# Send3.net
KiCad netlist of a schematic drawn in EAGLE
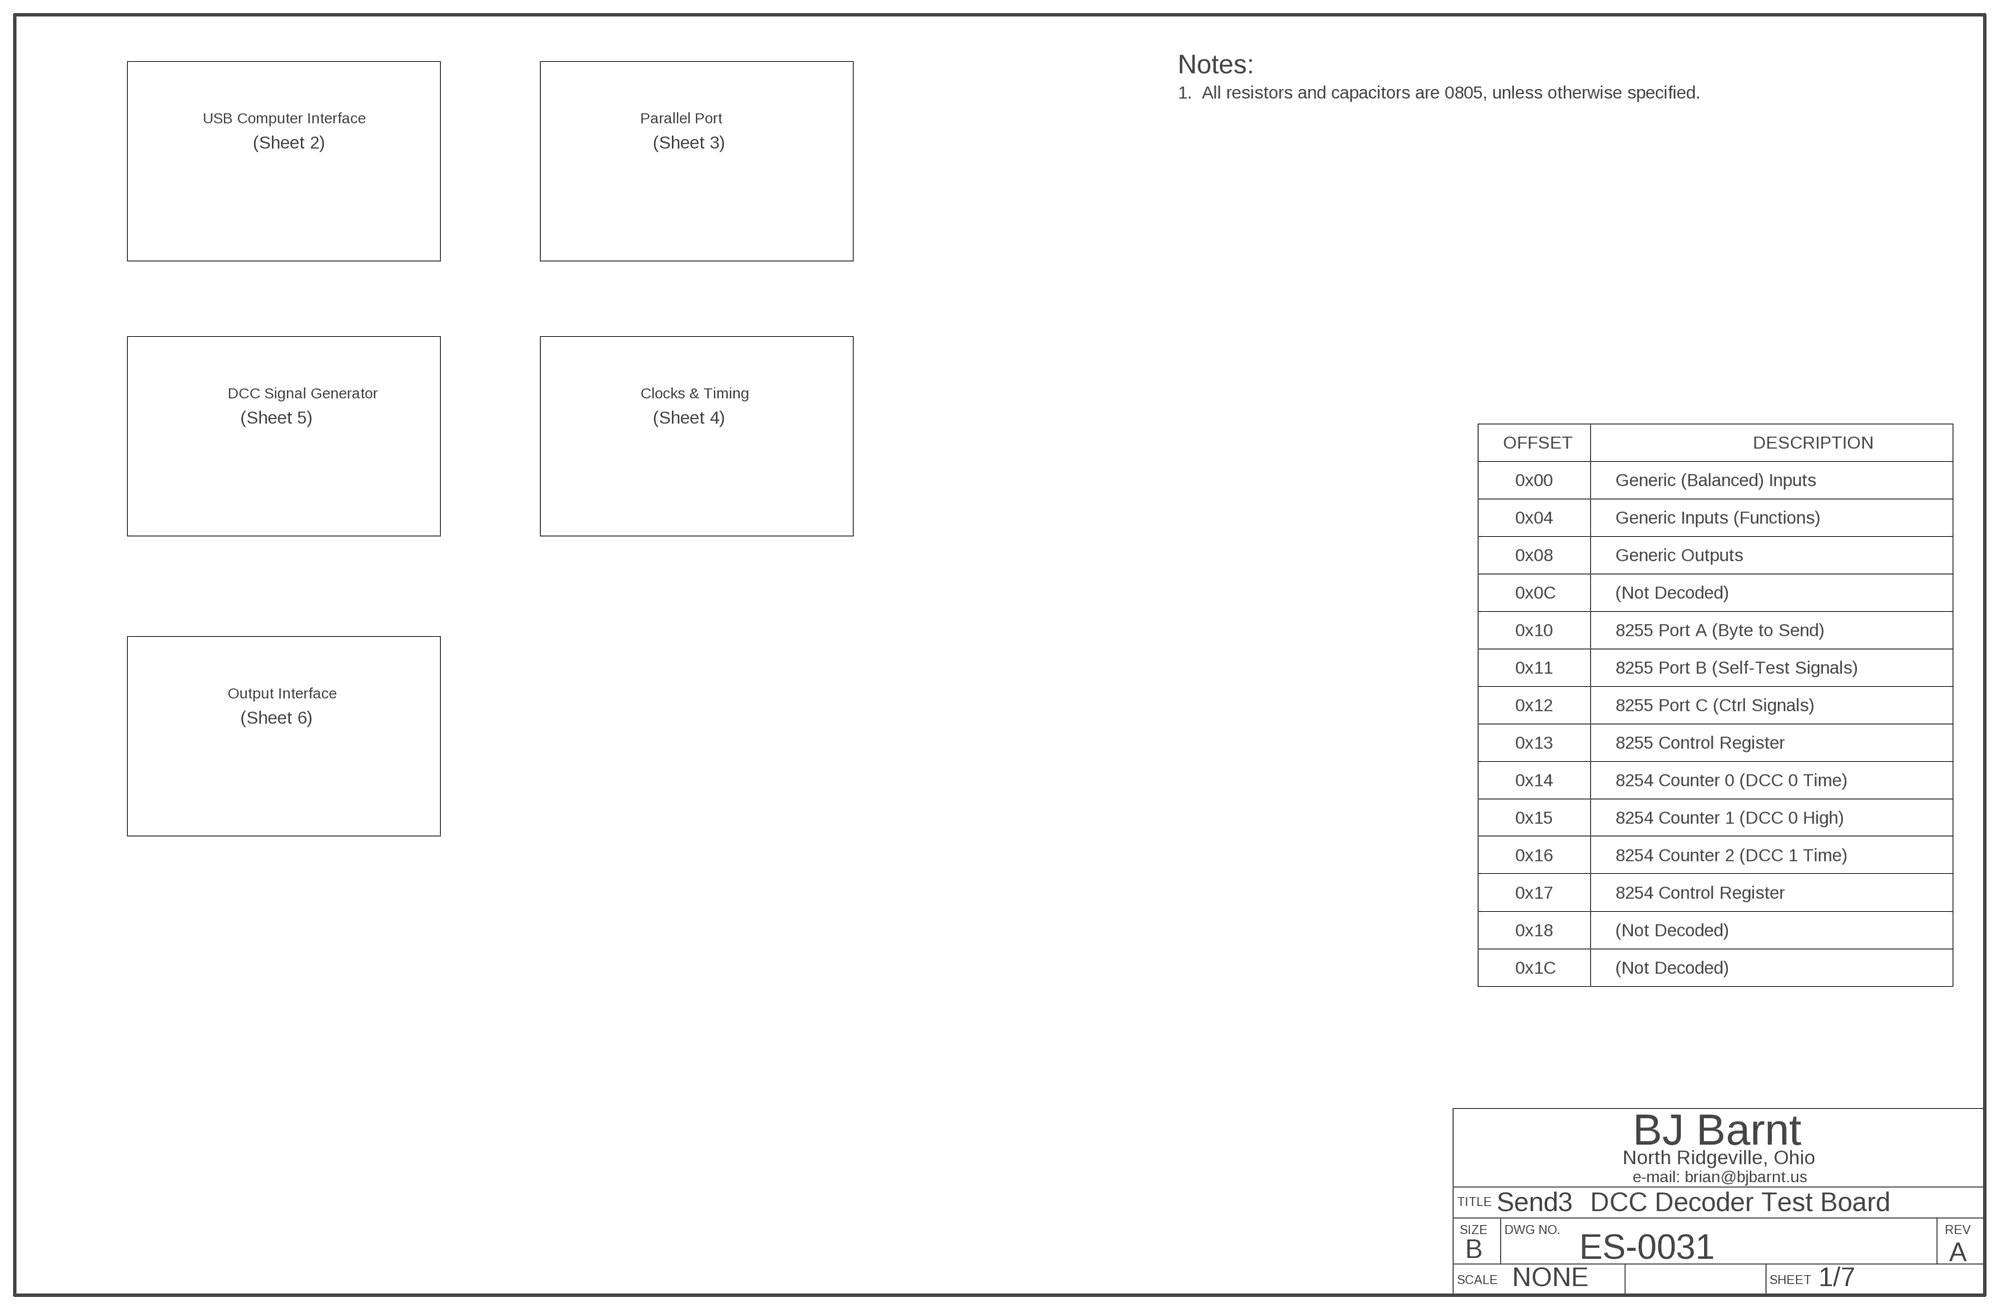
[diagram p0: schematic, sheet 1]
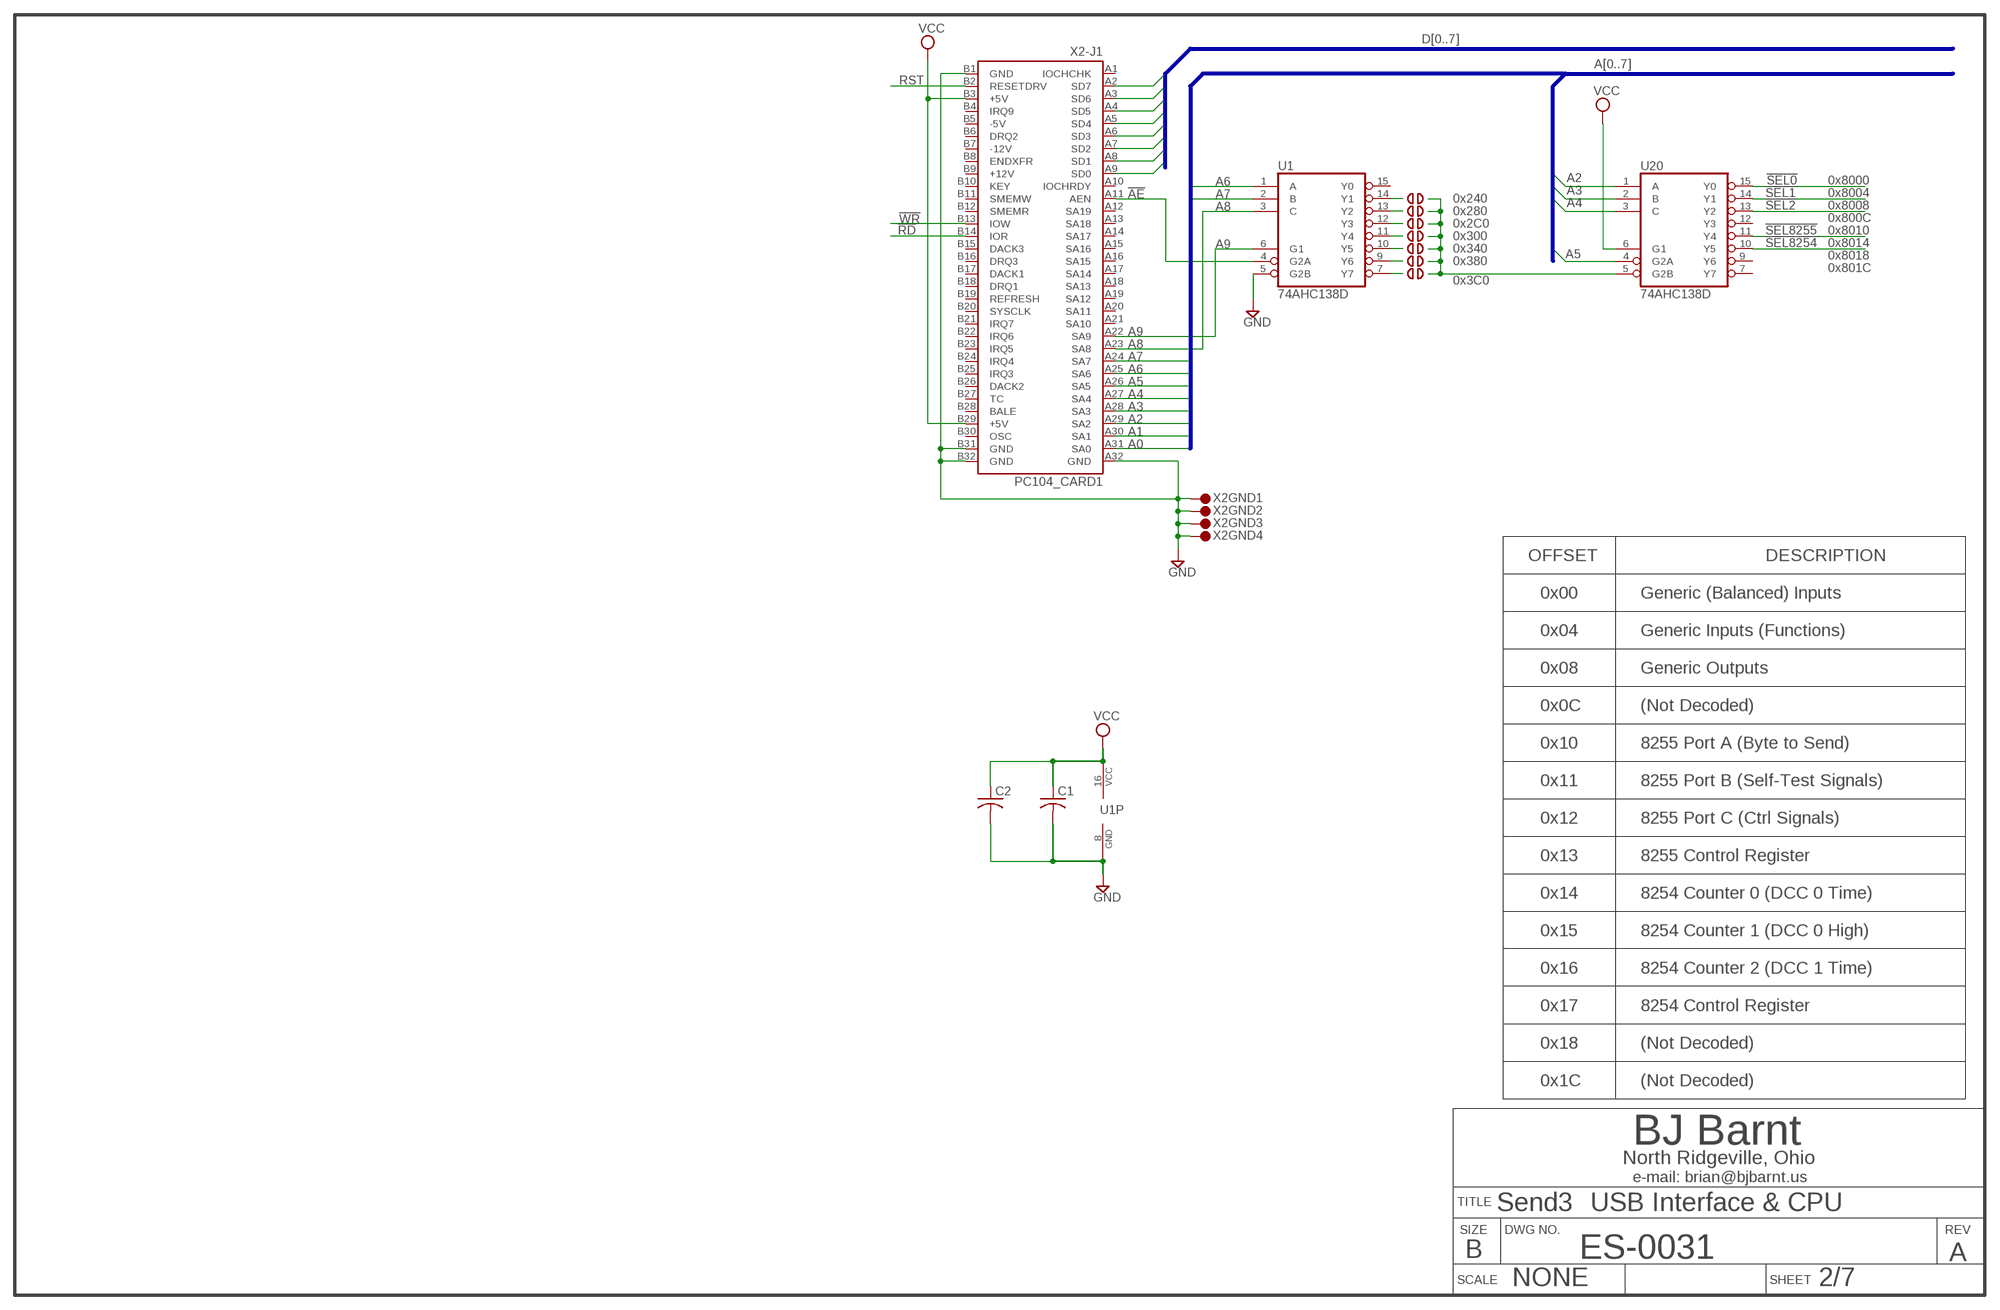
[diagram p1: schematic, sheet 2]
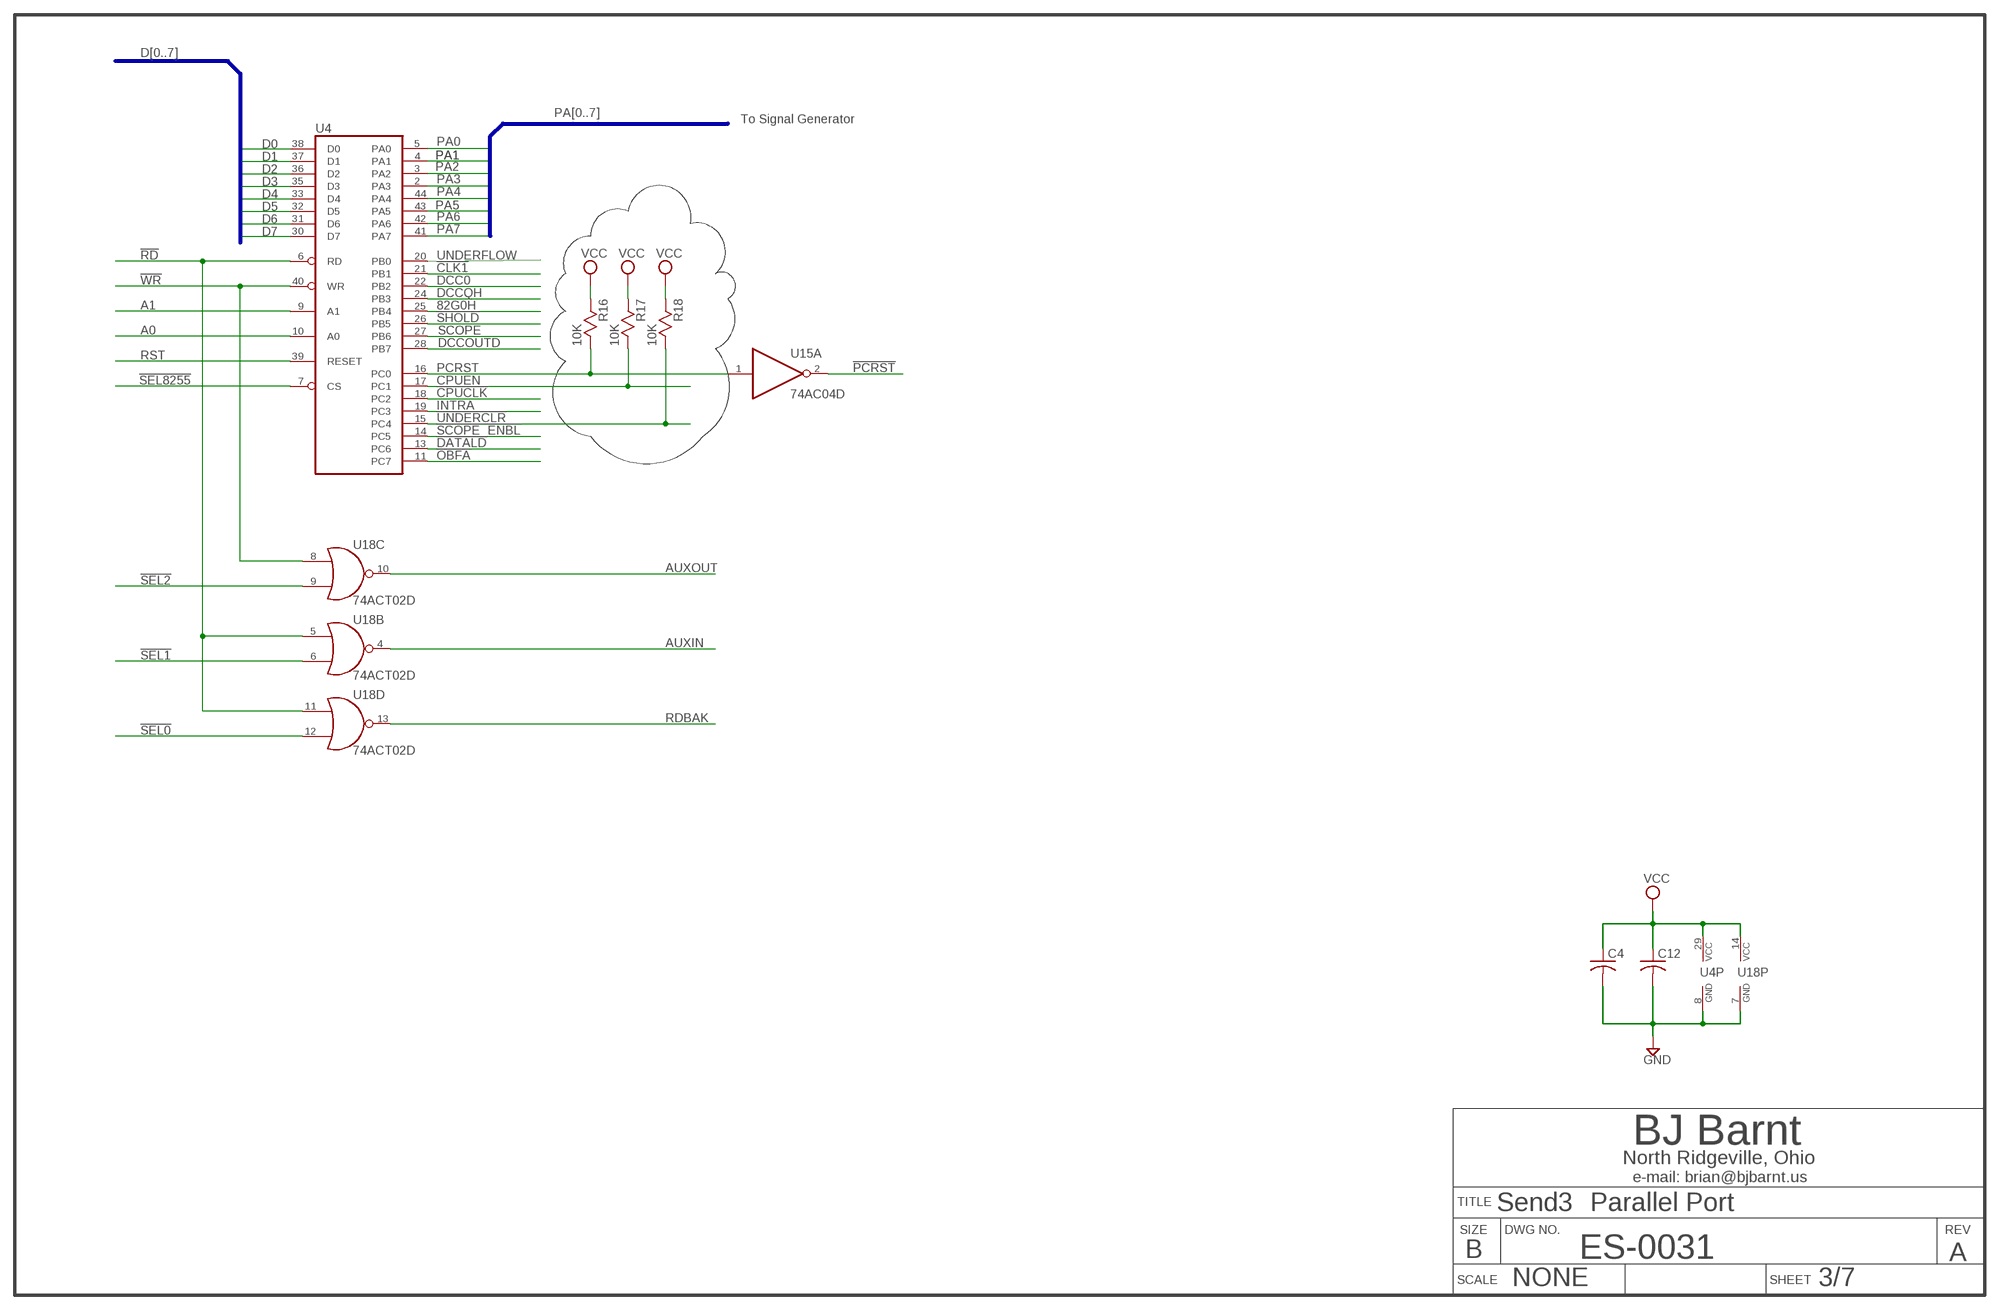
[diagram p2: schematic, sheet 3]
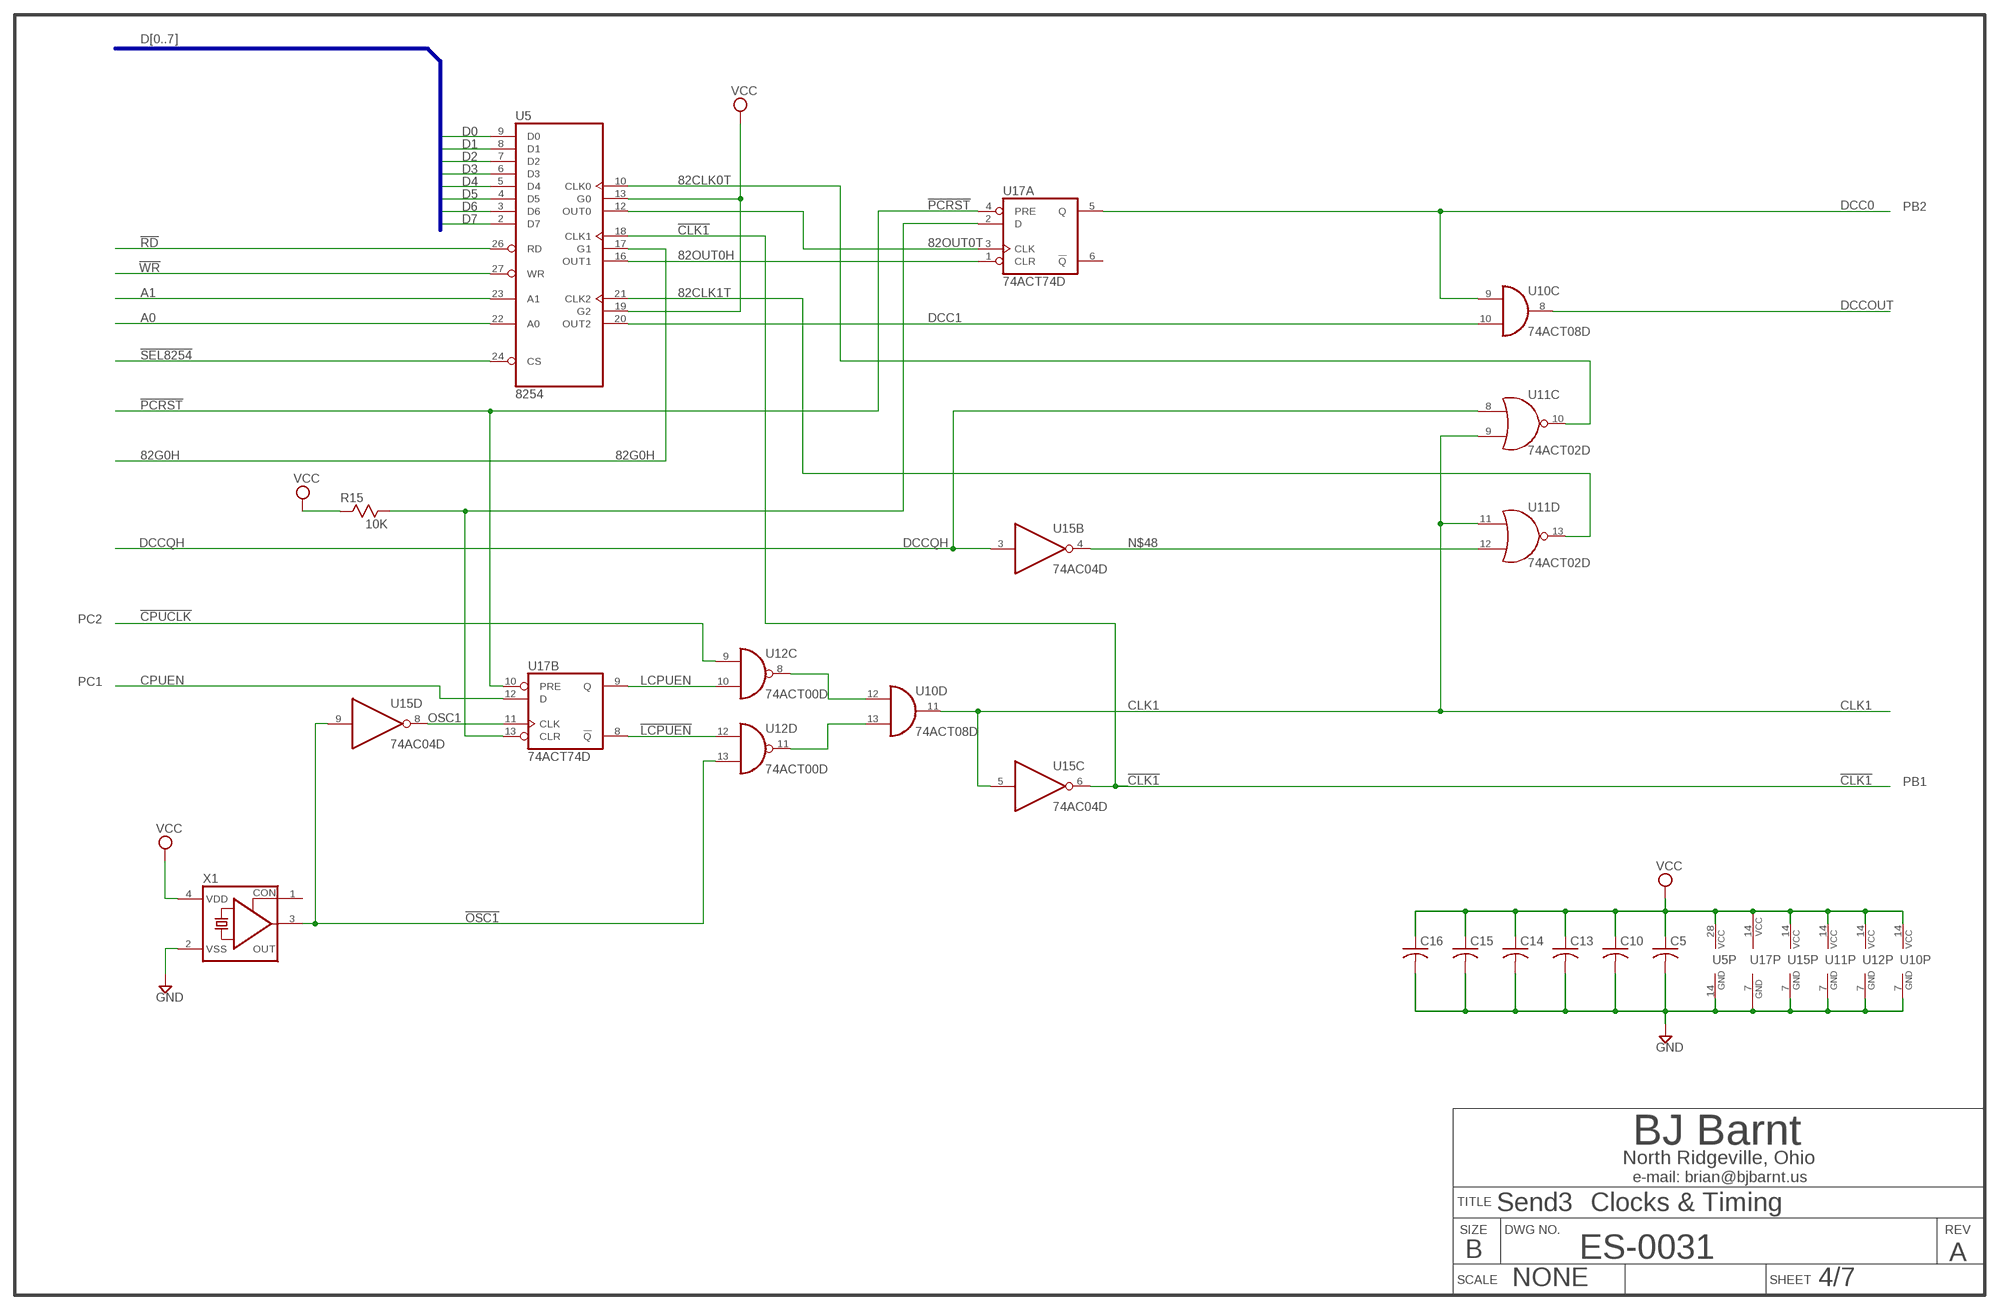
[diagram p3: schematic, sheet 4]
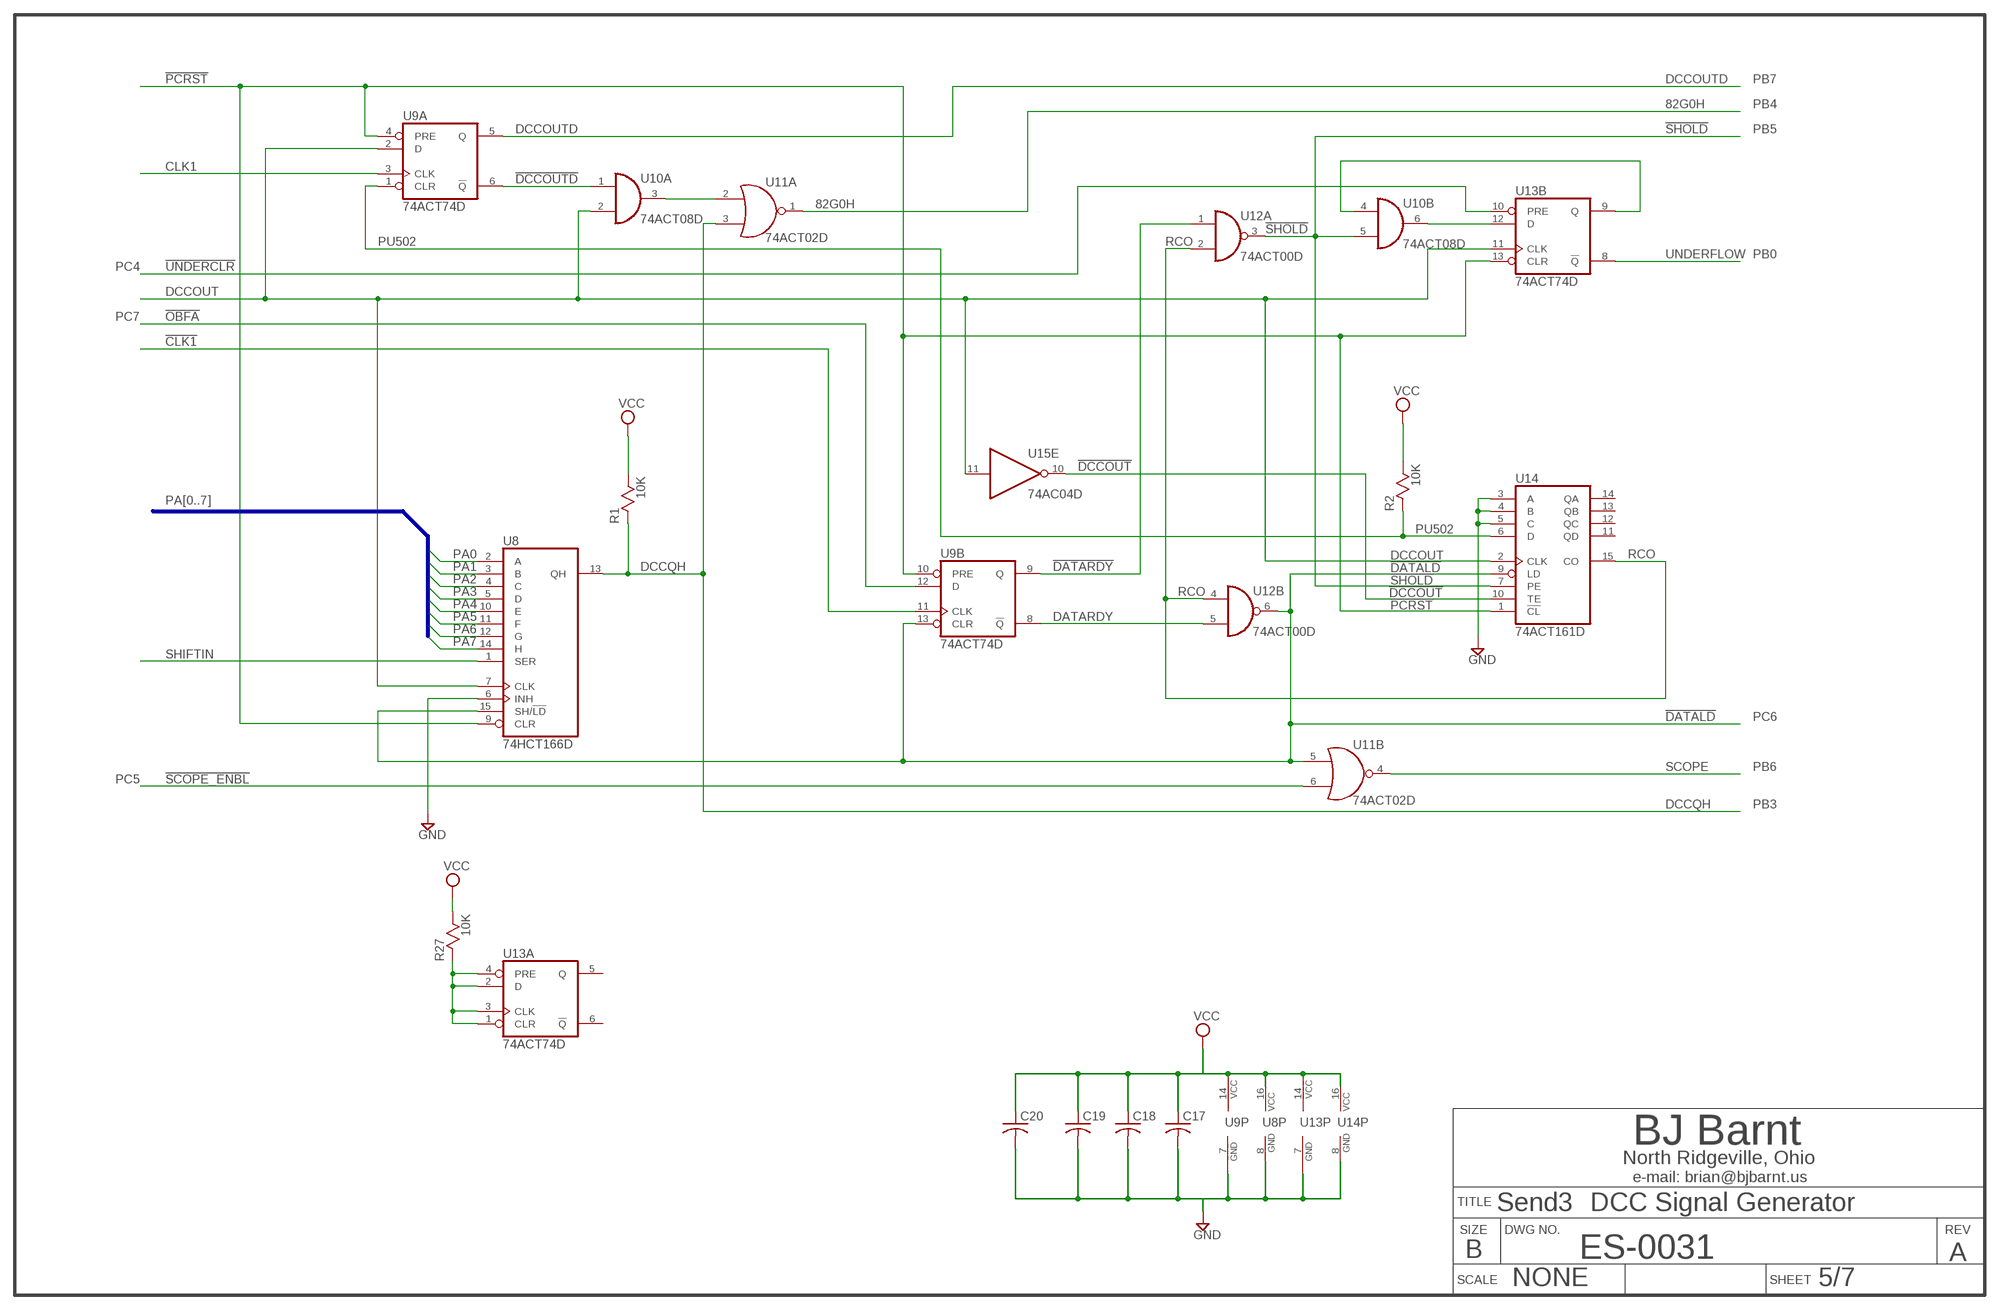
[diagram p4: schematic, sheet 5]
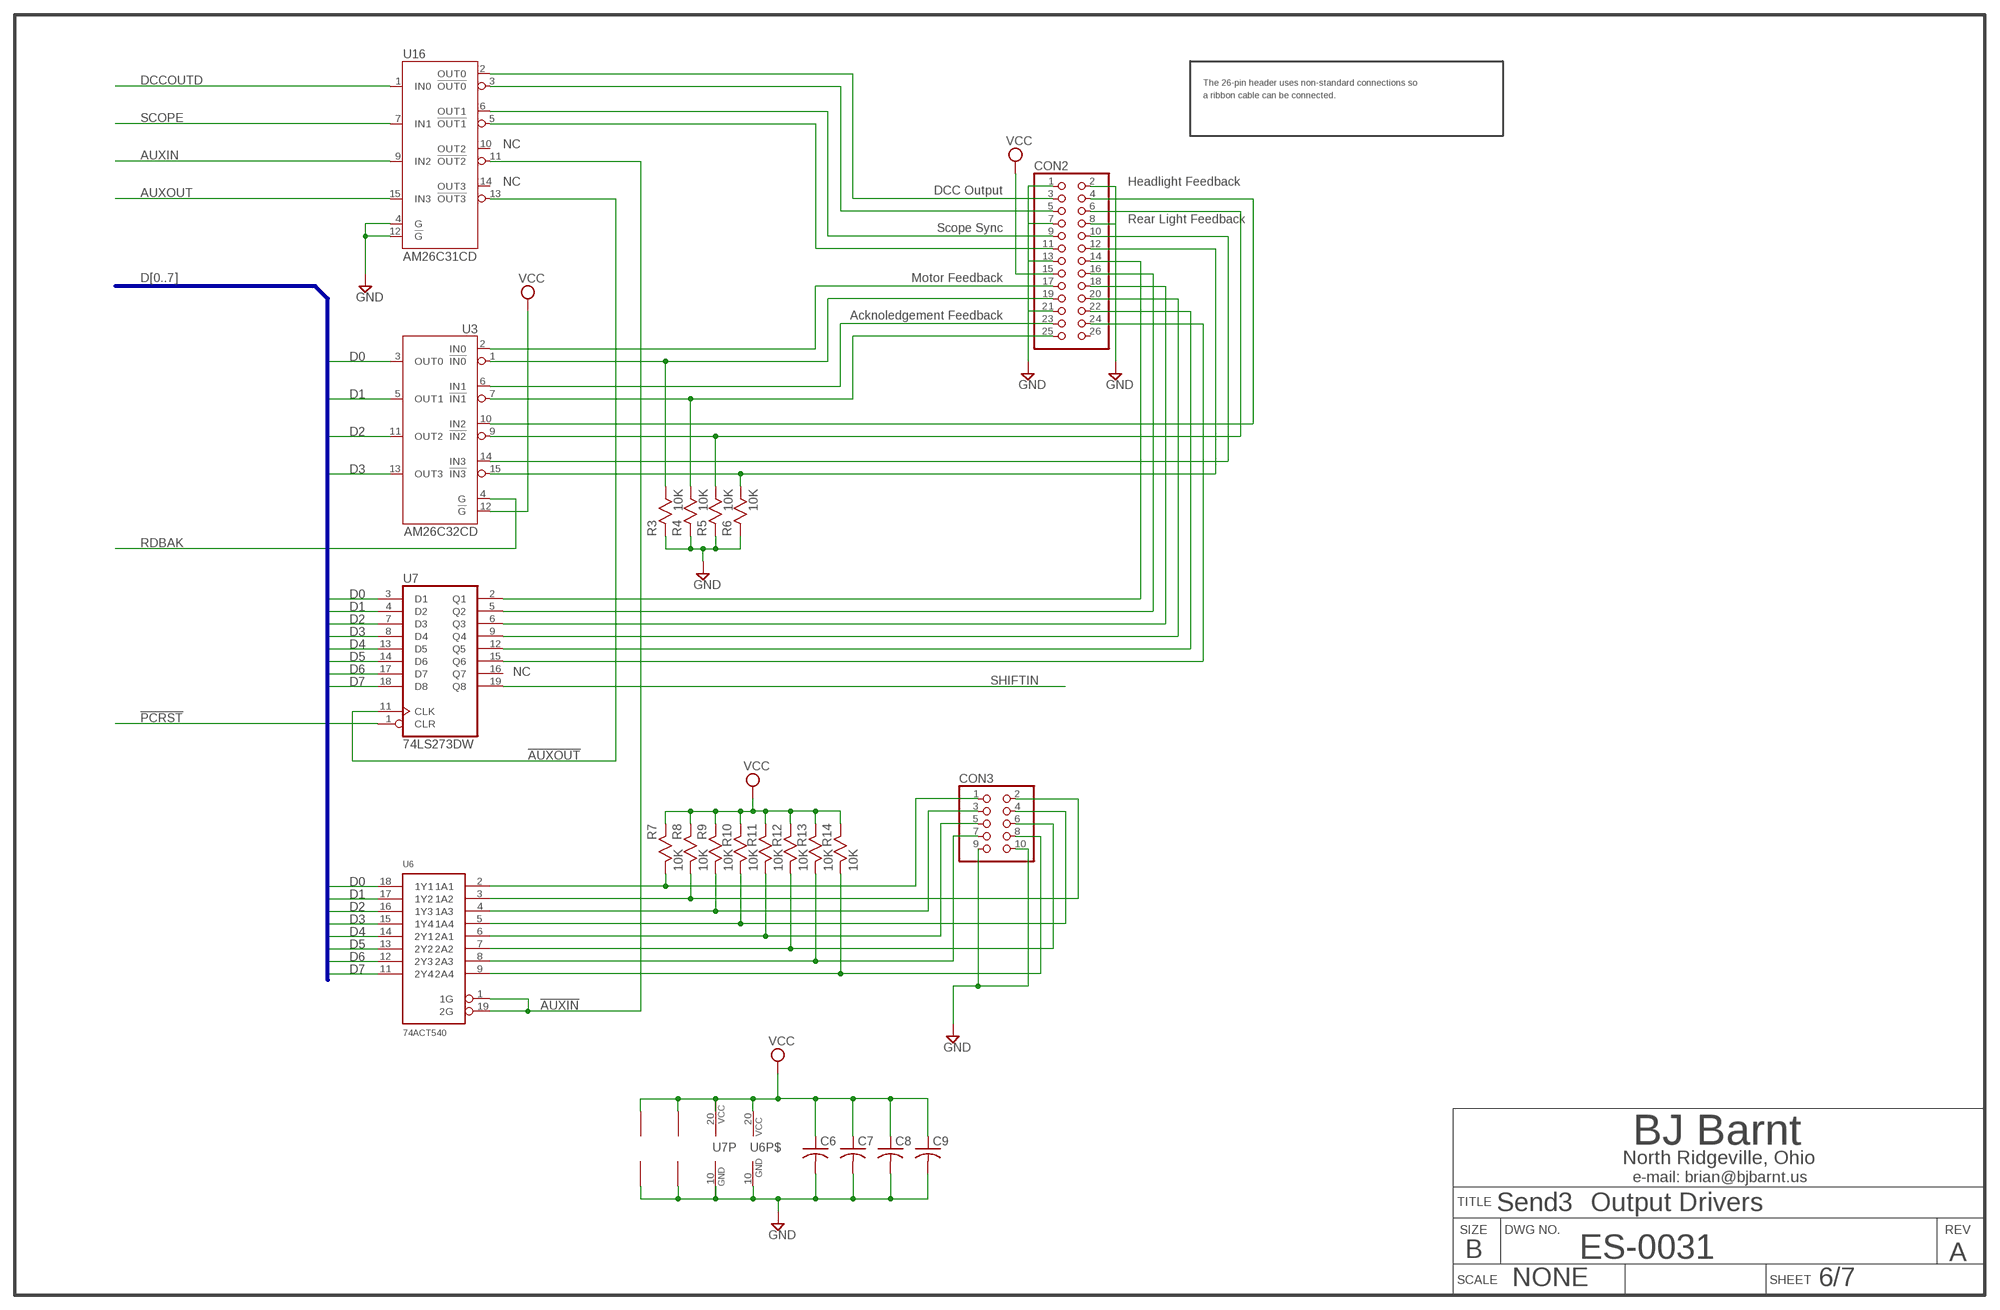
[diagram p5: schematic, sheet 6]
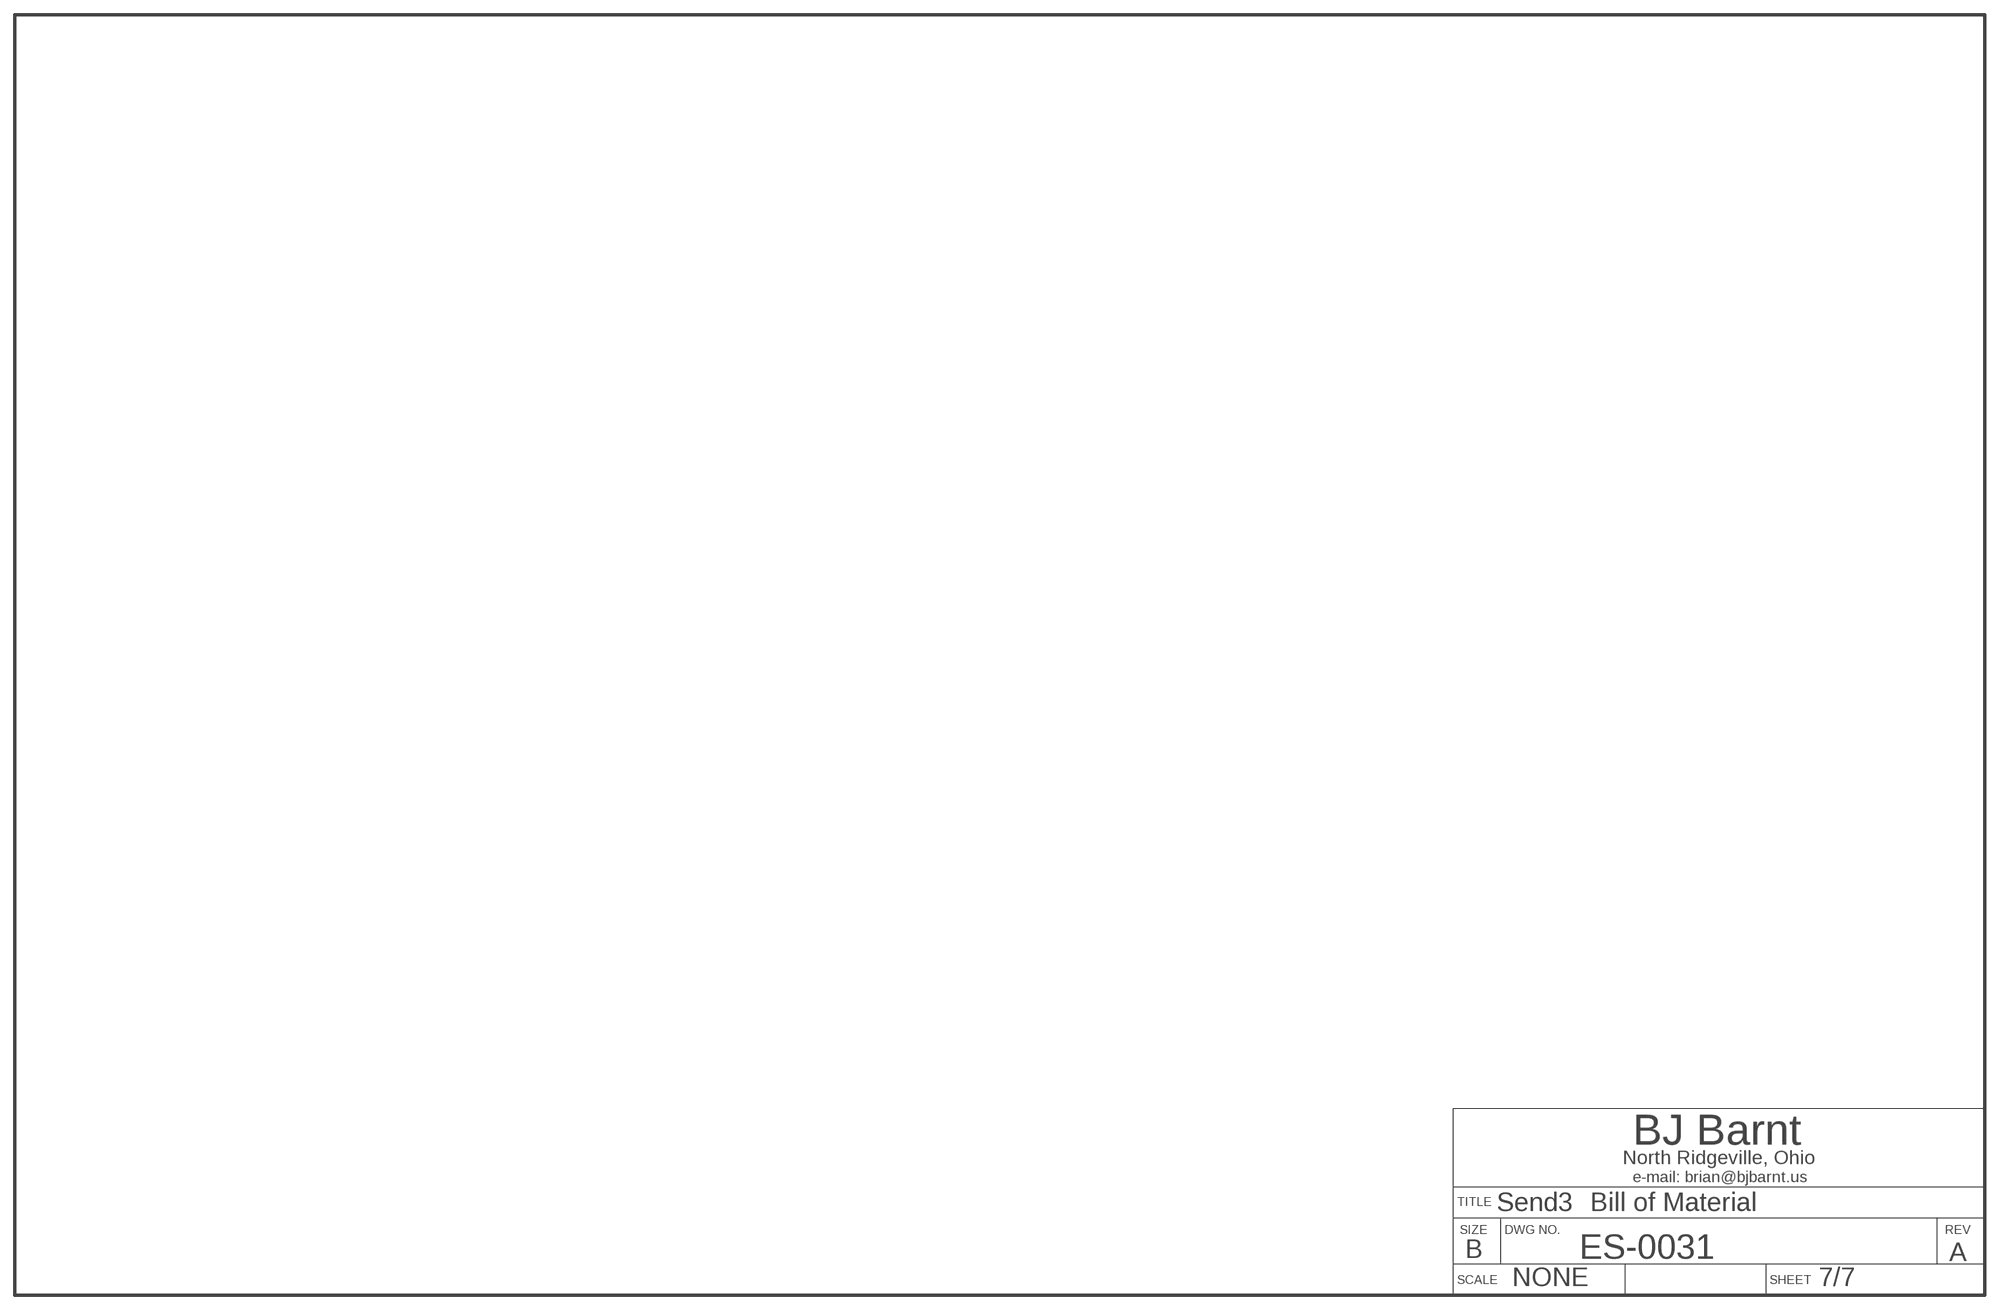
[diagram p6: schematic, sheet 7]

(export (version "E")
  (design (tool "Eeschema 10.0.6"))
  (components
    (comp (ref "C5")
      (value "C-USC0805K")
      (footprint "eagle-import:C0805K")
      (fields (field (name "MFG") "Panasonic"))
      (libsource (lib "eagle-import") (part "C-USC0805K"))
    )
    (comp (ref "C10")
      (value "C-USC0805K")
      (footprint "eagle-import:C0805K")
      (fields (field (name "MFG") "Panasonic"))
      (libsource (lib "eagle-import") (part "C-USC0805K"))
    )
    (comp (ref "C13")
      (value "C-USC0805K")
      (footprint "eagle-import:C0805K")
      (fields (field (name "MFG") "Panasonic"))
      (libsource (lib "eagle-import") (part "C-USC0805K"))
    )
    (comp (ref "C14")
      (value "C-USC0805K")
      (footprint "eagle-import:C0805K")
      (fields (field (name "MFG") "Panasonic"))
      (libsource (lib "eagle-import") (part "C-USC0805K"))
    )
    (comp (ref "C15")
      (value "C-USC0805K")
      (footprint "eagle-import:C0805K")
      (fields (field (name "MFG") "Panasonic"))
      (libsource (lib "eagle-import") (part "C-USC0805K"))
    )
    (comp (ref "C16")
      (value "C-USC0805K")
      (footprint "eagle-import:C0805K")
      (fields (field (name "MFG") "Panasonic"))
      (libsource (lib "eagle-import") (part "C-USC0805K"))
    )
    (comp (ref "R15")
      (value "10K")
      (footprint "eagle-import:R0805W")
      (fields (field (name "MFG") "Panasonic"))
      (libsource (lib "eagle-import") (part "R-US_0805W"))
    )
    (comp (ref "U5")
      (value "8254")
      (footprint "eagle-import:PLCC28S")
      (fields
        (field (name "DIST") "Digikey")
        (field (name "DIST_PN") "CS82C54-10Z96CT-ND")
        (field (name "MFG") "Intersil")
        (field (name "MFG_PN") "CS82C54-10Z96")
      )
      (libsource (lib "eagle-import") (part "8254"))
    )
    (comp (ref "U10")
      (value "74ACT08D")
      (footprint "eagle-import:SO14")
      (fields
        (field (name "DIST") "Digikey")
        (field (name "DIST_PN") "296-4523-1-ND")
        (field (name "MFG") "Texas Instruments")
        (field (name "MFG_PN") "SN74AHC08DR")
      )
      (libsource (lib "eagle-import") (part "7408DAC"))
    )
    (comp (ref "U11")
      (value "74ACT02D")
      (footprint "eagle-import:SO14")
      (fields
        (field (name "DIST") "Digikey")
        (field (name "DIST_PN") "296-4511-1-ND")
        (field (name "MFG") "Texas Instruments")
        (field (name "MFG_PN") "SN74AHC02DR")
      )
      (libsource (lib "eagle-import") (part "7402DAC"))
    )
    (comp (ref "U12")
      (value "74ACT00D")
      (footprint "eagle-import:SO14")
      (fields
        (field (name "MFG") "Texas Instruments")
        (field (name "DIST") "Digikey")
        (field (name "DIST_PN") "296-4509-1-ND")
        (field (name "MFG_PN") "SN74AHC00DR")
      )
      (libsource (lib "eagle-import") (part "7400DAC"))
    )
    (comp (ref "U15")
      (value "74AC04D")
      (footprint "eagle-import:SO14")
      (fields
        (field (name "DIST") "Digikey")
        (field (name "DIST_PN") "296-4516-2-ND")
        (field (name "MFG") "Texas Instruments")
        (field (name "MFG_PN") "SN74AHC04DR")
      )
      (libsource (lib "eagle-import") (part "7404DAC"))
    )
    (comp (ref "U17")
      (value "74ACT74D")
      (footprint "eagle-import:SO14")
      (fields
        (field (name "DIST") "Digikey")
        (field (name "DIST_PN") "296-1105-1-ND")
        (field (name "MFG") "Texas Instruments")
        (field (name "MFG_PN") "SN74AHC74DR")
      )
      (libsource (lib "eagle-import") (part "7474D"))
    )
    (comp (ref "X1")
      (value "CRYSTAL_RES-1100S")
      (footprint "eagle-import:1100S")
      (fields (field (name "MFG") "ECS"))
      (libsource (lib "eagle-import") (part "CRYSTAL_RES-1100S"))
    )
    (comp (ref "C4")
      (value "C-USC0805K")
      (footprint "eagle-import:C0805K")
      (fields (field (name "MFG") "Panasonic"))
      (libsource (lib "eagle-import") (part "C-USC0805K"))
    )
    (comp (ref "C12")
      (value "C-USC0805K")
      (footprint "eagle-import:C0805K")
      (fields (field (name "MFG") "Panasonic"))
      (libsource (lib "eagle-import") (part "C-USC0805K"))
    )
    (comp (ref "R16")
      (value "10K")
      (footprint "eagle-import:R0805W")
      (fields (field (name "MFG") "Panasonic"))
      (libsource (lib "eagle-import") (part "R-US_0805W"))
    )
    (comp (ref "R17")
      (value "10K")
      (footprint "eagle-import:R0805W")
      (fields (field (name "MFG") "Panasonic"))
      (libsource (lib "eagle-import") (part "R-US_0805W"))
    )
    (comp (ref "R18")
      (value "10K")
      (footprint "eagle-import:R0805W")
      (fields (field (name "MFG") "Panasonic"))
      (libsource (lib "eagle-import") (part "R-US_0805W"))
    )
    (comp (ref "U4")
      (value "8255A-S")
      (footprint "eagle-import:PLCC44")
      (fields
        (field (name "MFG") "Intersil")
        (field (name "DIST") "Digikey")
        (field (name "DIST_PN") "CQ82C55AZ-ND")
        (field (name "MFG_PN") "CQ82C55AZ")
      )
      (libsource (lib "eagle-import") (part "8255A-S"))
    )
    (comp (ref "U18")
      (value "74ACT02D")
      (footprint "eagle-import:SO14")
      (fields
        (field (name "DIST") "Digikey")
        (field (name "DIST_PN") "296-4511-1-ND")
        (field (name "MFG") "Texas Instruments")
        (field (name "MFG_PN") "SN74AHC02DR")
      )
      (libsource (lib "eagle-import") (part "7402DACT"))
    )
    (comp (ref "C17")
      (value "C-USC0805K")
      (footprint "eagle-import:C0805K")
      (fields (field (name "MFG") "Panasonic"))
      (libsource (lib "eagle-import") (part "C-USC0805K"))
    )
    (comp (ref "C18")
      (value "C-USC0805K")
      (footprint "eagle-import:C0805K")
      (fields (field (name "MFG") "Panasonic"))
      (libsource (lib "eagle-import") (part "C-USC0805K"))
    )
    (comp (ref "C19")
      (value "C-USC0805K")
      (footprint "eagle-import:C0805K")
      (fields (field (name "MFG") "Panasonic"))
      (libsource (lib "eagle-import") (part "C-USC0805K"))
    )
    (comp (ref "C20")
      (value "C-USC0805K")
      (footprint "eagle-import:C0805K")
      (fields (field (name "MFG") "Panasonic"))
      (libsource (lib "eagle-import") (part "C-USC0805K"))
    )
    (comp (ref "R1")
      (value "10K")
      (footprint "eagle-import:R0805W")
      (fields (field (name "MFG") "Panasonic"))
      (libsource (lib "eagle-import") (part "R-US_0805W"))
    )
    (comp (ref "R2")
      (value "10K")
      (footprint "eagle-import:R0805W")
      (fields (field (name "MFG") "Panasonic"))
      (libsource (lib "eagle-import") (part "R-US_0805W"))
    )
    (comp (ref "R27")
      (value "10K")
      (footprint "eagle-import:R0805W")
      (fields (field (name "MFG") "Panasonic"))
      (libsource (lib "eagle-import") (part "R-US_0805W"))
    )
    (comp (ref "U8")
      (value "74HCT166D")
      (footprint "eagle-import:SO16")
      (fields
        (field (name "DIST") "Digikey")
        (field (name "DIST_PN") "296-14839-1-ND")
        (field (name "MFG") "Texas Instruments")
        (field (name "MFG_PN") "SN74HC166DR")
      )
      (libsource (lib "eagle-import") (part "74166DHCT"))
    )
    (comp (ref "U9")
      (value "74ACT74D")
      (footprint "eagle-import:SO14")
      (fields
        (field (name "DIST") "Digikey")
        (field (name "DIST_PN") "296-1105-1-ND")
        (field (name "MFG") "Texas Instruments")
        (field (name "MFG_PN") "SN74AHC74DR")
      )
      (libsource (lib "eagle-import") (part "7474D"))
    )
    (comp (ref "U13")
      (value "74ACT74D")
      (footprint "eagle-import:SO14")
      (fields
        (field (name "DIST") "Digikey")
        (field (name "DIST_PN") "296-1105-1-ND")
        (field (name "MFG") "Texas Instruments")
        (field (name "MFG_PN") "SN74AHC74DR")
      )
      (libsource (lib "eagle-import") (part "7474D"))
    )
    (comp (ref "U14")
      (value "74ACT161D")
      (footprint "eagle-import:SO16")
      (fields
        (field (name "MFG") "Texas Instruments")
        (field (name "DIST") "Digikey")
        (field (name "DIST_PN") "296-4263-5-ND")
        (field (name "MFG_PN") "CD74ACT161M")
      )
      (libsource (lib "eagle-import") (part "74161D"))
    )
    (comp (ref "C6")
      (value "C-USC0805K")
      (footprint "eagle-import:C0805K")
      (fields (field (name "MFG") "Panasonic"))
      (libsource (lib "eagle-import") (part "C-USC0805K"))
    )
    (comp (ref "C7")
      (value "C-USC0805K")
      (footprint "eagle-import:C0805K")
      (fields (field (name "MFG") "Panasonic"))
      (libsource (lib "eagle-import") (part "C-USC0805K"))
    )
    (comp (ref "C8")
      (value "C-USC0805K")
      (footprint "eagle-import:C0805K")
      (fields (field (name "MFG") "Panasonic"))
      (libsource (lib "eagle-import") (part "C-USC0805K"))
    )
    (comp (ref "C9")
      (value "C-USC0805K")
      (footprint "eagle-import:C0805K")
      (fields (field (name "MFG") "Panasonic"))
      (libsource (lib "eagle-import") (part "C-USC0805K"))
    )
    (comp (ref "CON2")
      (value "PINHD-2X13")
      (footprint "eagle-import:2X13")
      (fields (field (name "MFG") "Sullins"))
      (libsource (lib "eagle-import") (part "PINHD-2X13"))
    )
    (comp (ref "CON3")
      (value "PINHD-2X5")
      (footprint "eagle-import:2X05")
      (libsource (lib "eagle-import") (part "PINHD-2X5"))
    )
    (comp (ref "R3")
      (value "10K")
      (footprint "eagle-import:R0805W")
      (fields (field (name "MFG") "Panasonic"))
      (libsource (lib "eagle-import") (part "R-US_0805W"))
    )
    (comp (ref "R4")
      (value "10K")
      (footprint "eagle-import:R0805W")
      (fields (field (name "MFG") "Panasonic"))
      (libsource (lib "eagle-import") (part "R-US_0805W"))
    )
    (comp (ref "R5")
      (value "10K")
      (footprint "eagle-import:R0805W")
      (fields (field (name "MFG") "Panasonic"))
      (libsource (lib "eagle-import") (part "R-US_0805W"))
    )
    (comp (ref "R6")
      (value "10K")
      (footprint "eagle-import:R0805W")
      (fields (field (name "MFG") "Panasonic"))
      (libsource (lib "eagle-import") (part "R-US_0805W"))
    )
    (comp (ref "R7")
      (value "10K")
      (footprint "eagle-import:R0805W")
      (fields (field (name "MFG") "Panasonic"))
      (libsource (lib "eagle-import") (part "R-US_0805W"))
    )
    (comp (ref "R8")
      (value "10K")
      (footprint "eagle-import:R0805W")
      (fields (field (name "MFG") "Panasonic"))
      (libsource (lib "eagle-import") (part "R-US_0805W"))
    )
    (comp (ref "R9")
      (value "10K")
      (footprint "eagle-import:R0805W")
      (fields (field (name "MFG") "Panasonic"))
      (libsource (lib "eagle-import") (part "R-US_0805W"))
    )
    (comp (ref "R10")
      (value "10K")
      (footprint "eagle-import:R0805W")
      (fields (field (name "MFG") "Panasonic"))
      (libsource (lib "eagle-import") (part "R-US_0805W"))
    )
    (comp (ref "R11")
      (value "10K")
      (footprint "eagle-import:R0805W")
      (fields (field (name "MFG") "Panasonic"))
      (libsource (lib "eagle-import") (part "R-US_0805W"))
    )
    (comp (ref "R12")
      (value "10K")
      (footprint "eagle-import:R0805W")
      (fields (field (name "MFG") "Panasonic"))
      (libsource (lib "eagle-import") (part "R-US_0805W"))
    )
    (comp (ref "R13")
      (value "10K")
      (footprint "eagle-import:R0805W")
      (fields (field (name "MFG") "Panasonic"))
      (libsource (lib "eagle-import") (part "R-US_0805W"))
    )
    (comp (ref "R14")
      (value "10K")
      (footprint "eagle-import:R0805W")
      (fields (field (name "MFG") "Panasonic"))
      (libsource (lib "eagle-import") (part "R-US_0805W"))
    )
    (comp (ref "U3")
      (value "AM26C32CD")
      (footprint "eagle-import:SO16")
      (fields
        (field (name "DIST") "Digikey")
        (field (name "DIST_PN") "296-6786-5-ND")
        (field (name "MFG") "Texas Instruments")
        (field (name "MFG_PN") "AM26C32CD")
      )
      (libsource (lib "eagle-import") (part "AM26C32CD"))
    )
    (comp (ref "U6")
      (value "74ACT540")
      (footprint "eagle-import:SO20W")
      (fields
        (field (name "DIST") "Digikey")
        (field (name "DIST_PN") "296-4605-1-ND")
        (field (name "MFG") "Texas Instruments")
        (field (name "MFG_PN") "SN74AHC540DWR")
      )
      (libsource (lib "eagle-import") (part "74540"))
    )
    (comp (ref "U7")
      (value "74LS273DW")
      (footprint "eagle-import:SO20W")
      (fields
        (field (name "DIST") "Digikey")
        (field (name "DIST_PN") "296-26512-5-ND")
        (field (name "MFG") "Texas Instruments")
        (field (name "MFG_PN") "SN74LS273DW")
      )
      (libsource (lib "eagle-import") (part "74273DWLS"))
    )
    (comp (ref "U16")
      (value "AM26C31CD")
      (footprint "eagle-import:SO16")
      (fields
        (field (name "DIST") "Digikey")
        (field (name "DIST_PN") "296-22029-1-ND")
        (field (name "MFG") "Texas Instruments")
        (field (name "MFG_PN") "AM26C31QDRG4")
      )
      (libsource (lib "eagle-import") (part "AM26C31CD"))
    )
    (comp (ref "C1")
      (value "C-USC0805K")
      (footprint "eagle-import:C0805K")
      (fields (field (name "MFG") "Panasonic"))
      (libsource (lib "eagle-import") (part "C-USC0805K"))
    )
    (comp (ref "C2")
      (value "C-USC0805K")
      (footprint "eagle-import:C0805K")
      (fields (field (name "MFG") "Panasonic"))
      (libsource (lib "eagle-import") (part "C-USC0805K"))
    )
    (comp (ref "JMPR2")
      (value "JUMPER")
      (footprint "eagle-import:SOLDER_BRIDGE")
      (libsource (lib "eagle-import") (part "JUMPER"))
    )
    (comp (ref "JMPR3")
      (value "JUMPER")
      (footprint "eagle-import:SOLDER_BRIDGE")
      (libsource (lib "eagle-import") (part "JUMPER"))
    )
    (comp (ref "JMPR4")
      (value "JUMPER")
      (footprint "eagle-import:SOLDER_BRIDGE")
      (libsource (lib "eagle-import") (part "JUMPER"))
    )
    (comp (ref "JMPR5")
      (value "JUMPER")
      (footprint "eagle-import:SOLDER_BRIDGE")
      (libsource (lib "eagle-import") (part "JUMPER"))
    )
    (comp (ref "JMPR6")
      (value "JUMPER")
      (footprint "eagle-import:SOLDER_BRIDGE")
      (libsource (lib "eagle-import") (part "JUMPER"))
    )
    (comp (ref "JMPR7")
      (value "JUMPER")
      (footprint "eagle-import:SOLDER_BRIDGE")
      (libsource (lib "eagle-import") (part "JUMPER"))
    )
    (comp (ref "JMPR8")
      (value "JUMPER")
      (footprint "eagle-import:SOLDER_BRIDGE")
      (libsource (lib "eagle-import") (part "JUMPER"))
    )
    (comp (ref "U1")
      (value "74AHC138D")
      (footprint "eagle-import:SO16")
      (fields
        (field (name "DIST") "Digikey")
        (field (name "DIST_PN") "296-4540-5-ND")
        (field (name "MFG") "Texas Instruments")
        (field (name "MFG_PN") "SN74AHC138D")
      )
      (libsource (lib "eagle-import") (part "74138DAHC"))
    )
    (comp (ref "U20")
      (value "74AHC138D")
      (footprint "eagle-import:SO16")
      (fields (field (name "MFG") "Texas Instruments"))
      (libsource (lib "eagle-import") (part "74138DAHC"))
    )
    (comp (ref "X2")
      (value "PC104_CARD1")
      (footprint "eagle-import:PC104-STANDARD")
      (libsource (lib "eagle-import") (part "PC104_CARD1"))
    )
  )
  (nets
    (net (code "8") (name "82CLK0T") (class "Default")
      (node (ref "U11") (pin "10") (pinfunction "O_10") (pintype "output"))
      (node (ref "U5") (pin "10") (pinfunction "CLK0_10") (pintype "bidirectional"))
    )
    (net (code "9") (name "82CLK1T") (class "Default")
      (node (ref "U11") (pin "13") (pinfunction "O_13") (pintype "output"))
      (node (ref "U5") (pin "21") (pinfunction "CLK2_21") (pintype "bidirectional"))
    )
    (net (code "10") (name "82G0H") (class "Default")
      (node (ref "U11") (pin "1") (pinfunction "O_1") (pintype "output"))
      (node (ref "U4") (pin "25") (pinfunction "PB4_25") (pintype "bidirectional"))
      (node (ref "U5") (pin "17") (pinfunction "G1_17") (pintype "bidirectional"))
    )
    (net (code "11") (name "82OUT0H") (class "Default")
      (node (ref "U17") (pin "1") (pinfunction "CLR_1") (pintype "input"))
      (node (ref "U5") (pin "16") (pinfunction "OUT1_16") (pintype "bidirectional"))
    )
    (net (code "12") (name "82OUT0T") (class "Default")
      (node (ref "U17") (pin "3") (pinfunction "CLK_3") (pintype "input"))
      (node (ref "U5") (pin "12") (pinfunction "OUT0_12") (pintype "bidirectional"))
    )
    (net (code "13") (name "A0") (class "Default")
      (node (ref "U4") (pin "10") (pinfunction "A0_10") (pintype "input"))
      (node (ref "U5") (pin "22") (pinfunction "A0_22") (pintype "input"))
      (node (ref "X2") (pin "A31") (pinfunction "SA0_A31") (pintype "passive"))
    )
    (net (code "14") (name "A1") (class "Default")
      (node (ref "U4") (pin "9") (pinfunction "A1_9") (pintype "input"))
      (node (ref "U5") (pin "23") (pinfunction "A1_23") (pintype "input"))
      (node (ref "X2") (pin "A30") (pinfunction "SA1_A30") (pintype "passive"))
    )
    (net (code "15") (name "A2") (class "Default")
      (node (ref "U20") (pin "1") (pinfunction "A_1") (pintype "input"))
      (node (ref "X2") (pin "A29") (pinfunction "SA2_A29") (pintype "passive"))
    )
    (net (code "16") (name "A3") (class "Default")
      (node (ref "U20") (pin "2") (pinfunction "B_2") (pintype "input"))
      (node (ref "X2") (pin "A28") (pinfunction "SA3_A28") (pintype "passive"))
    )
    (net (code "17") (name "A4") (class "Default")
      (node (ref "U20") (pin "3") (pinfunction "C_3") (pintype "input"))
      (node (ref "X2") (pin "A27") (pinfunction "SA4_A27") (pintype "passive"))
    )
    (net (code "18") (name "A5") (class "Default")
      (node (ref "U20") (pin "4") (pinfunction "G2A_4") (pintype "input"))
      (node (ref "X2") (pin "A26") (pinfunction "SA5_A26") (pintype "passive"))
    )
    (net (code "19") (name "A6") (class "Default")
      (node (ref "U1") (pin "1") (pinfunction "A_1") (pintype "input"))
      (node (ref "X2") (pin "A25") (pinfunction "SA6_A25") (pintype "passive"))
    )
    (net (code "20") (name "A7") (class "Default")
      (node (ref "U1") (pin "2") (pinfunction "B_2") (pintype "input"))
      (node (ref "X2") (pin "A24") (pinfunction "SA7_A24") (pintype "passive"))
    )
    (net (code "21") (name "A8") (class "Default")
      (node (ref "U1") (pin "3") (pinfunction "C_3") (pintype "input"))
      (node (ref "X2") (pin "A23") (pinfunction "SA8_A23") (pintype "passive"))
    )
    (net (code "22") (name "A9") (class "Default")
      (node (ref "U1") (pin "6") (pinfunction "G1_6") (pintype "input"))
      (node (ref "X2") (pin "A22") (pinfunction "SA9_A22") (pintype "passive"))
    )
    (net (code "23") (name "AUXIN") (class "Default")
      (node (ref "U16") (pin "9") (pinfunction "IN2_9") (pintype "bidirectional"))
      (node (ref "U18") (pin "4") (pinfunction "O_4") (pintype "output"))
    )
    (net (code "24") (name "AUXOUT") (class "Default")
      (node (ref "U16") (pin "15") (pinfunction "IN3_15") (pintype "bidirectional"))
      (node (ref "U18") (pin "10") (pinfunction "O_10") (pintype "output"))
    )
    (net (code "25") (name "CLK1") (class "Default")
      (node (ref "U10") (pin "11") (pinfunction "O_11") (pintype "output"))
      (node (ref "U11") (pin "11") (pinfunction "I0_11") (pintype "input"))
      (node (ref "U11") (pin "9") (pinfunction "I1_9") (pintype "input"))
      (node (ref "U15") (pin "5") (pinfunction "I_5") (pintype "input"))
      (node (ref "U9") (pin "3") (pinfunction "CLK_3") (pintype "input"))
    )
    (net (code "26") (name "CPUEN") (class "Default")
      (node (ref "R17") (pin "2") (pinfunction "2_2") (pintype "passive"))
      (node (ref "U17") (pin "12") (pinfunction "D_12") (pintype "input"))
      (node (ref "U4") (pin "17") (pinfunction "PC1_17") (pintype "bidirectional"))
    )
    (net (code "27") (name "D0") (class "Default")
      (node (ref "U3") (pin "3") (pinfunction "OUT0_3") (pintype "bidirectional"))
      (node (ref "U4") (pin "38") (pinfunction "D0_38") (pintype "bidirectional"))
      (node (ref "U5") (pin "9") (pinfunction "D0_9") (pintype "bidirectional"))
      (node (ref "U6") (pin "18") (pinfunction "1Y1_18") (pintype "bidirectional"))
      (node (ref "U7") (pin "3") (pinfunction "D1_3") (pintype "input"))
      (node (ref "X2") (pin "A9") (pinfunction "SD0_A9") (pintype "passive"))
    )
    (net (code "28") (name "D1") (class "Default")
      (node (ref "U3") (pin "5") (pinfunction "OUT1_5") (pintype "bidirectional"))
      (node (ref "U4") (pin "37") (pinfunction "D1_37") (pintype "bidirectional"))
      (node (ref "U5") (pin "8") (pinfunction "D1_8") (pintype "bidirectional"))
      (node (ref "U6") (pin "17") (pinfunction "1Y2_17") (pintype "bidirectional"))
      (node (ref "U7") (pin "4") (pinfunction "D2_4") (pintype "input"))
      (node (ref "X2") (pin "A8") (pinfunction "SD1_A8") (pintype "passive"))
    )
    (net (code "29") (name "D2") (class "Default")
      (node (ref "U3") (pin "11") (pinfunction "OUT2_11") (pintype "bidirectional"))
      (node (ref "U4") (pin "36") (pinfunction "D2_36") (pintype "bidirectional"))
      (node (ref "U5") (pin "7") (pinfunction "D2_7") (pintype "bidirectional"))
      (node (ref "U6") (pin "16") (pinfunction "1Y3_16") (pintype "bidirectional"))
      (node (ref "U7") (pin "7") (pinfunction "D3_7") (pintype "input"))
      (node (ref "X2") (pin "A7") (pinfunction "SD2_A7") (pintype "passive"))
    )
    (net (code "30") (name "D3") (class "Default")
      (node (ref "U3") (pin "13") (pinfunction "OUT3_13") (pintype "bidirectional"))
      (node (ref "U4") (pin "35") (pinfunction "D3_35") (pintype "bidirectional"))
      (node (ref "U5") (pin "6") (pinfunction "D3_6") (pintype "bidirectional"))
      (node (ref "U6") (pin "15") (pinfunction "1Y4_15") (pintype "bidirectional"))
      (node (ref "U7") (pin "8") (pinfunction "D4_8") (pintype "input"))
      (node (ref "X2") (pin "A6") (pinfunction "SD3_A6") (pintype "passive"))
    )
    (net (code "31") (name "D4") (class "Default")
      (node (ref "U4") (pin "33") (pinfunction "D4_33") (pintype "bidirectional"))
      (node (ref "U5") (pin "5") (pinfunction "D4_5") (pintype "bidirectional"))
      (node (ref "U6") (pin "14") (pinfunction "2Y1_14") (pintype "bidirectional"))
      (node (ref "U7") (pin "13") (pinfunction "D5_13") (pintype "input"))
      (node (ref "X2") (pin "A5") (pinfunction "SD4_A5") (pintype "passive"))
    )
    (net (code "32") (name "D5") (class "Default")
      (node (ref "U4") (pin "32") (pinfunction "D5_32") (pintype "bidirectional"))
      (node (ref "U5") (pin "4") (pinfunction "D5_4") (pintype "bidirectional"))
      (node (ref "U6") (pin "13") (pinfunction "2Y2_13") (pintype "bidirectional"))
      (node (ref "U7") (pin "14") (pinfunction "D6_14") (pintype "input"))
      (node (ref "X2") (pin "A4") (pinfunction "SD5_A4") (pintype "passive"))
    )
    (net (code "33") (name "D6") (class "Default")
      (node (ref "U4") (pin "31") (pinfunction "D6_31") (pintype "bidirectional"))
      (node (ref "U5") (pin "3") (pinfunction "D6_3") (pintype "bidirectional"))
      (node (ref "U6") (pin "12") (pinfunction "2Y3_12") (pintype "bidirectional"))
      (node (ref "U7") (pin "17") (pinfunction "D7_17") (pintype "input"))
      (node (ref "X2") (pin "A3") (pinfunction "SD6_A3") (pintype "passive"))
    )
    (net (code "34") (name "D7") (class "Default")
      (node (ref "U4") (pin "30") (pinfunction "D7_30") (pintype "bidirectional"))
      (node (ref "U5") (pin "2") (pinfunction "D7_2") (pintype "bidirectional"))
      (node (ref "U6") (pin "11") (pinfunction "2Y4_11") (pintype "bidirectional"))
      (node (ref "U7") (pin "18") (pinfunction "D8_18") (pintype "input"))
      (node (ref "X2") (pin "A2") (pinfunction "SD7_A2") (pintype "passive"))
    )
    (net (code "35") (name "DATARDY") (class "Default")
      (node (ref "U12") (pin "5") (pinfunction "I1_5") (pintype "input"))
      (node (ref "U9") (pin "8") (pinfunction "~{Q}_8") (pintype "output"))
    )
    (net (code "36") (name "DCC0") (class "Default")
      (node (ref "U10") (pin "9") (pinfunction "I0_9") (pintype "input"))
      (node (ref "U17") (pin "5") (pinfunction "Q_5") (pintype "output"))
      (node (ref "U4") (pin "22") (pinfunction "PB2_22") (pintype "bidirectional"))
    )
    (net (code "37") (name "DCC1") (class "Default")
      (node (ref "U10") (pin "10") (pinfunction "I1_10") (pintype "input"))
      (node (ref "U5") (pin "20") (pinfunction "OUT2_20") (pintype "bidirectional"))
    )
    (net (code "38") (name "DCCOUT") (class "Default")
      (node (ref "U10") (pin "2") (pinfunction "I1_2") (pintype "input"))
      (node (ref "U10") (pin "8") (pinfunction "O_8") (pintype "output"))
      (node (ref "U13") (pin "11") (pinfunction "CLK_11") (pintype "input"))
      (node (ref "U14") (pin "2") (pinfunction "CLK_2") (pintype "input"))
      (node (ref "U15") (pin "11") (pinfunction "I_11") (pintype "input"))
      (node (ref "U8") (pin "7") (pinfunction "CLK_7") (pintype "input"))
      (node (ref "U9") (pin "2") (pinfunction "D_2") (pintype "input"))
    )
    (net (code "39") (name "DCCOUTD") (class "Default")
      (node (ref "U16") (pin "1") (pinfunction "IN0_1") (pintype "bidirectional"))
      (node (ref "U4") (pin "28") (pinfunction "PB7_28") (pintype "bidirectional"))
      (node (ref "U9") (pin "5") (pinfunction "Q_5") (pintype "output"))
    )
    (net (code "40") (name "DCCQH") (class "Default")
      (node (ref "R1") (pin "1") (pinfunction "1_1") (pintype "passive"))
      (node (ref "U11") (pin "3") (pinfunction "I1_3") (pintype "input"))
      (node (ref "U11") (pin "8") (pinfunction "I0_8") (pintype "input"))
      (node (ref "U15") (pin "3") (pinfunction "I_3") (pintype "input"))
      (node (ref "U4") (pin "24") (pinfunction "PB3_24") (pintype "bidirectional"))
      (node (ref "U8") (pin "13") (pinfunction "QH_13") (pintype "output"))
    )
    (net (code "41") (name "GND") (class "Default")
      (node (ref "C1") (pin "2") (pinfunction "2_2") (pintype "passive"))
      (node (ref "C10") (pin "2") (pinfunction "2_2") (pintype "passive"))
      (node (ref "C12") (pin "2") (pinfunction "2_2") (pintype "passive"))
      (node (ref "C13") (pin "2") (pinfunction "2_2") (pintype "passive"))
      (node (ref "C14") (pin "2") (pinfunction "2_2") (pintype "passive"))
      (node (ref "C15") (pin "2") (pinfunction "2_2") (pintype "passive"))
      (node (ref "C16") (pin "2") (pinfunction "2_2") (pintype "passive"))
      (node (ref "C17") (pin "2") (pinfunction "2_2") (pintype "passive"))
      (node (ref "C18") (pin "2") (pinfunction "2_2") (pintype "passive"))
      (node (ref "C19") (pin "2") (pinfunction "2_2") (pintype "passive"))
      (node (ref "C2") (pin "2") (pinfunction "2_2") (pintype "passive"))
      (node (ref "C20") (pin "2") (pinfunction "2_2") (pintype "passive"))
      (node (ref "C4") (pin "2") (pinfunction "2_2") (pintype "passive"))
      (node (ref "C5") (pin "2") (pinfunction "2_2") (pintype "passive"))
      (node (ref "C6") (pin "2") (pinfunction "2_2") (pintype "passive"))
      (node (ref "C7") (pin "2") (pinfunction "2_2") (pintype "passive"))
      (node (ref "C8") (pin "2") (pinfunction "2_2") (pintype "passive"))
      (node (ref "C9") (pin "2") (pinfunction "2_2") (pintype "passive"))
      (node (ref "CON2") (pin "1") (pinfunction "1_1") (pintype "passive"))
      (node (ref "CON2") (pin "13") (pinfunction "13_13") (pintype "passive"))
      (node (ref "CON2") (pin "2") (pinfunction "2_2") (pintype "passive"))
      (node (ref "CON2") (pin "21") (pinfunction "21_21") (pintype "passive"))
      (node (ref "CON2") (pin "7") (pinfunction "7_7") (pintype "passive"))
      (node (ref "CON2") (pin "8") (pinfunction "8_8") (pintype "passive"))
      (node (ref "CON3") (pin "10") (pinfunction "10_10") (pintype "passive"))
      (node (ref "CON3") (pin "9") (pinfunction "9_9") (pintype "passive"))
      (node (ref "R3") (pin "1") (pinfunction "1_1") (pintype "passive"))
      (node (ref "R4") (pin "1") (pinfunction "1_1") (pintype "passive"))
      (node (ref "R5") (pin "1") (pinfunction "1_1") (pintype "passive"))
      (node (ref "R6") (pin "1") (pinfunction "1_1") (pintype "passive"))
      (node (ref "U1") (pin "5") (pinfunction "G2B_5") (pintype "input"))
      (node (ref "U1") (pin "8") (pinfunction "GND_8") (pintype "power_in"))
      (node (ref "U10") (pin "7") (pinfunction "GND_7") (pintype "power_in"))
      (node (ref "U11") (pin "7") (pinfunction "GND_7") (pintype "power_in"))
      (node (ref "U12") (pin "7") (pinfunction "GND_7") (pintype "power_in"))
      (node (ref "U13") (pin "7") (pinfunction "GND_7") (pintype "power_in"))
      (node (ref "U14") (pin "3") (pinfunction "A_3") (pintype "input"))
      (node (ref "U14") (pin "4") (pinfunction "B_4") (pintype "input"))
      (node (ref "U14") (pin "5") (pinfunction "C_5") (pintype "input"))
      (node (ref "U14") (pin "8") (pinfunction "GND_8") (pintype "power_in"))
      (node (ref "U15") (pin "7") (pinfunction "GND_7") (pintype "power_in"))
      (node (ref "U16") (pin "12") (pinfunction "~{G}_12") (pintype "bidirectional"))
      (node (ref "U16") (pin "4") (pinfunction "G_4") (pintype "bidirectional"))
      (node (ref "U16") (pin "8") (pinfunction "GND_8") (pintype "power_in"))
      (node (ref "U17") (pin "7") (pinfunction "GND_7") (pintype "power_in"))
      (node (ref "U18") (pin "7") (pinfunction "GND_7") (pintype "power_in"))
      (node (ref "U3") (pin "8") (pinfunction "GND_8") (pintype "power_in"))
      (node (ref "U4") (pin "8") (pinfunction "GND_8") (pintype "power_in"))
      (node (ref "U5") (pin "14") (pinfunction "GND_14") (pintype "power_in"))
      (node (ref "U6") (pin "10") (pinfunction "GND_10") (pintype "power_in"))
      (node (ref "U7") (pin "10") (pinfunction "GND_10") (pintype "power_in"))
      (node (ref "U8") (pin "6") (pinfunction "INH_6") (pintype "input"))
      (node (ref "U8") (pin "8") (pinfunction "GND_8") (pintype "power_in"))
      (node (ref "U9") (pin "7") (pinfunction "GND_7") (pintype "power_in"))
      (node (ref "X1") (pin "2") (pinfunction "VSS_2") (pintype "power_in"))
      (node (ref "X2") (pin "A32") (pinfunction "GND_A32") (pintype "passive"))
      (node (ref "X2") (pin "B1") (pinfunction "GND_B1") (pintype "passive"))
      (node (ref "X2") (pin "B31") (pinfunction "GND_B31") (pintype "passive"))
      (node (ref "X2") (pin "B32") (pinfunction "GND_B32") (pintype "passive"))
      (node (ref "X2") (pin "GND@1") (pinfunction "1_GND@1") (pintype "passive"))
      (node (ref "X2") (pin "GND@2") (pinfunction "1_GND@2") (pintype "passive"))
      (node (ref "X2") (pin "GND@3") (pinfunction "1_GND@3") (pintype "passive"))
      (node (ref "X2") (pin "GND@4") (pinfunction "1_GND@4") (pintype "passive"))
    )
    (net (code "42") (name "INTRA") (class "Default")
      (node (ref "U4") (pin "19") (pinfunction "PC3_19") (pintype "bidirectional"))
    )
    (net (code "43") (name "LCPUEN") (class "Default")
      (node (ref "U12") (pin "10") (pinfunction "I1_10") (pintype "input"))
      (node (ref "U17") (pin "9") (pinfunction "Q_9") (pintype "output"))
    )
    (net (code "44") (name "N$48") (class "Default")
      (node (ref "U11") (pin "12") (pinfunction "I1_12") (pintype "input"))
      (node (ref "U15") (pin "4") (pinfunction "O_4") (pintype "output"))
    )
    (net (code "45") (name "Net-(U1A-Y1)") (class "Default")
      (node (ref "JMPR2") (pin "P$1") (pinfunction "P$1_P$1") (pintype "passive"))
      (node (ref "U1") (pin "14") (pinfunction "Y1_14") (pintype "output"))
    )
    (net (code "46") (name "Net-(U1A-Y2)") (class "Default")
      (node (ref "JMPR3") (pin "P$1") (pinfunction "P$1_P$1") (pintype "passive"))
      (node (ref "U1") (pin "13") (pinfunction "Y2_13") (pintype "output"))
    )
    (net (code "47") (name "Net-(U1A-Y3)") (class "Default")
      (node (ref "JMPR4") (pin "P$1") (pinfunction "P$1_P$1") (pintype "passive"))
      (node (ref "U1") (pin "12") (pinfunction "Y3_12") (pintype "output"))
    )
    (net (code "48") (name "Net-(U1A-Y4)") (class "Default")
      (node (ref "JMPR5") (pin "P$1") (pinfunction "P$1_P$1") (pintype "passive"))
      (node (ref "U1") (pin "11") (pinfunction "Y4_11") (pintype "output"))
    )
    (net (code "49") (name "Net-(U1A-Y5)") (class "Default")
      (node (ref "JMPR6") (pin "P$1") (pinfunction "P$1_P$1") (pintype "passive"))
      (node (ref "U1") (pin "10") (pinfunction "Y5_10") (pintype "output"))
    )
    (net (code "50") (name "Net-(U1A-Y6)") (class "Default")
      (node (ref "JMPR7") (pin "P$1") (pinfunction "P$1_P$1") (pintype "passive"))
      (node (ref "U1") (pin "9") (pinfunction "Y6_9") (pintype "output"))
    )
    (net (code "51") (name "Net-(U1A-Y7)") (class "Default")
      (node (ref "JMPR8") (pin "P$1") (pinfunction "P$1_P$1") (pintype "passive"))
      (node (ref "U1") (pin "7") (pinfunction "Y7_7") (pintype "output"))
    )
    (net (code "52") (name "Net-(U3A-IN0)") (class "Default")
      (node (ref "CON2") (pin "17") (pinfunction "17_17") (pintype "passive"))
      (node (ref "U3") (pin "2") (pinfunction "IN0_2") (pintype "bidirectional"))
    )
    (net (code "53") (name "Net-(U3A-IN1)") (class "Default")
      (node (ref "CON2") (pin "23") (pinfunction "23_23") (pintype "passive"))
      (node (ref "U3") (pin "6") (pinfunction "IN1_6") (pintype "bidirectional"))
    )
    (net (code "54") (name "Net-(U3A-IN2)") (class "Default")
      (node (ref "CON2") (pin "4") (pinfunction "4_4") (pintype "passive"))
      (node (ref "U3") (pin "10") (pinfunction "IN2_10") (pintype "bidirectional"))
    )
    (net (code "55") (name "Net-(U3A-IN3)") (class "Default")
      (node (ref "CON2") (pin "10") (pinfunction "10_10") (pintype "passive"))
      (node (ref "U3") (pin "14") (pinfunction "IN3_14") (pintype "bidirectional"))
    )
    (net (code "56") (name "Net-(U3A-~{IN0})") (class "Default")
      (node (ref "CON2") (pin "19") (pinfunction "19_19") (pintype "passive"))
      (node (ref "R3") (pin "2") (pinfunction "2_2") (pintype "passive"))
      (node (ref "U3") (pin "1") (pinfunction "~{IN0}_1") (pintype "bidirectional"))
    )
    (net (code "57") (name "Net-(U3A-~{IN1})") (class "Default")
      (node (ref "CON2") (pin "25") (pinfunction "25_25") (pintype "passive"))
      (node (ref "R4") (pin "2") (pinfunction "2_2") (pintype "passive"))
      (node (ref "U3") (pin "7") (pinfunction "~{IN1}_7") (pintype "bidirectional"))
    )
    (net (code "58") (name "Net-(U3A-~{IN2})") (class "Default")
      (node (ref "CON2") (pin "6") (pinfunction "6_6") (pintype "passive"))
      (node (ref "R5") (pin "2") (pinfunction "2_2") (pintype "passive"))
      (node (ref "U3") (pin "9") (pinfunction "~{IN2}_9") (pintype "bidirectional"))
    )
    (net (code "59") (name "Net-(U3A-~{IN3})") (class "Default")
      (node (ref "CON2") (pin "12") (pinfunction "12_12") (pintype "passive"))
      (node (ref "R6") (pin "2") (pinfunction "2_2") (pintype "passive"))
      (node (ref "U3") (pin "15") (pinfunction "~{IN3}_15") (pintype "bidirectional"))
    )
    (net (code "60") (name "Net-(U6A-1A1)") (class "Default")
      (node (ref "CON3") (pin "1") (pinfunction "1_1") (pintype "passive"))
      (node (ref "R7") (pin "2") (pinfunction "2_2") (pintype "passive"))
      (node (ref "U6") (pin "2") (pinfunction "1A1_2") (pintype "bidirectional"))
    )
    (net (code "61") (name "Net-(U6A-1A2)") (class "Default")
      (node (ref "CON3") (pin "2") (pinfunction "2_2") (pintype "passive"))
      (node (ref "R8") (pin "2") (pinfunction "2_2") (pintype "passive"))
      (node (ref "U6") (pin "3") (pinfunction "1A2_3") (pintype "bidirectional"))
    )
    (net (code "62") (name "Net-(U6A-1A3)") (class "Default")
      (node (ref "CON3") (pin "3") (pinfunction "3_3") (pintype "passive"))
      (node (ref "R9") (pin "2") (pinfunction "2_2") (pintype "passive"))
      (node (ref "U6") (pin "4") (pinfunction "1A3_4") (pintype "bidirectional"))
    )
    (net (code "63") (name "Net-(U6A-1A4)") (class "Default")
      (node (ref "CON3") (pin "4") (pinfunction "4_4") (pintype "passive"))
      (node (ref "R10") (pin "2") (pinfunction "2_2") (pintype "passive"))
      (node (ref "U6") (pin "5") (pinfunction "1A4_5") (pintype "bidirectional"))
    )
    (net (code "64") (name "Net-(U6A-2A1)") (class "Default")
      (node (ref "CON3") (pin "5") (pinfunction "5_5") (pintype "passive"))
      (node (ref "R11") (pin "2") (pinfunction "2_2") (pintype "passive"))
      (node (ref "U6") (pin "6") (pinfunction "2A1_6") (pintype "bidirectional"))
    )
    (net (code "65") (name "Net-(U6A-2A2)") (class "Default")
      (node (ref "CON3") (pin "6") (pinfunction "6_6") (pintype "passive"))
      (node (ref "R12") (pin "2") (pinfunction "2_2") (pintype "passive"))
      (node (ref "U6") (pin "7") (pinfunction "2A2_7") (pintype "bidirectional"))
    )
    (net (code "66") (name "Net-(U6A-2A3)") (class "Default")
      (node (ref "CON3") (pin "7") (pinfunction "7_7") (pintype "passive"))
      (node (ref "R13") (pin "2") (pinfunction "2_2") (pintype "passive"))
      (node (ref "U6") (pin "8") (pinfunction "2A3_8") (pintype "bidirectional"))
    )
    (net (code "67") (name "Net-(U6A-2A4)") (class "Default")
      (node (ref "CON3") (pin "8") (pinfunction "8_8") (pintype "passive"))
      (node (ref "R14") (pin "2") (pinfunction "2_2") (pintype "passive"))
      (node (ref "U6") (pin "9") (pinfunction "2A4_9") (pintype "bidirectional"))
    )
    (net (code "68") (name "Net-(U7A-Q1)") (class "Default")
      (node (ref "CON2") (pin "14") (pinfunction "14_14") (pintype "passive"))
      (node (ref "U7") (pin "2") (pinfunction "Q1_2") (pintype "output"))
    )
    (net (code "69") (name "Net-(U7A-Q2)") (class "Default")
      (node (ref "CON2") (pin "16") (pinfunction "16_16") (pintype "passive"))
      (node (ref "U7") (pin "5") (pinfunction "Q2_5") (pintype "output"))
    )
    (net (code "70") (name "Net-(U7A-Q3)") (class "Default")
      (node (ref "CON2") (pin "18") (pinfunction "18_18") (pintype "passive"))
      (node (ref "U7") (pin "6") (pinfunction "Q3_6") (pintype "output"))
    )
    (net (code "71") (name "Net-(U7A-Q4)") (class "Default")
      (node (ref "CON2") (pin "20") (pinfunction "20_20") (pintype "passive"))
      (node (ref "U7") (pin "9") (pinfunction "Q4_9") (pintype "output"))
    )
    (net (code "72") (name "Net-(U7A-Q5)") (class "Default")
      (node (ref "CON2") (pin "22") (pinfunction "22_22") (pintype "passive"))
      (node (ref "U7") (pin "12") (pinfunction "Q5_12") (pintype "output"))
    )
    (net (code "73") (name "Net-(U7A-Q6)") (class "Default")
      (node (ref "CON2") (pin "24") (pinfunction "24_24") (pintype "passive"))
      (node (ref "U7") (pin "15") (pinfunction "Q6_15") (pintype "output"))
    )
    (net (code "74") (name "Net-(U10A-O)") (class "Default")
      (node (ref "U10") (pin "3") (pinfunction "O_3") (pintype "output"))
      (node (ref "U11") (pin "2") (pinfunction "I0_2") (pintype "input"))
    )
    (net (code "75") (name "Net-(U10B-I0)") (class "Default")
      (node (ref "U10") (pin "4") (pinfunction "I0_4") (pintype "input"))
      (node (ref "U13") (pin "9") (pinfunction "Q_9") (pintype "output"))
    )
    (net (code "76") (name "Net-(U10B-O)") (class "Default")
      (node (ref "U10") (pin "6") (pinfunction "O_6") (pintype "output"))
      (node (ref "U13") (pin "12") (pinfunction "D_12") (pintype "input"))
    )
    (net (code "77") (name "Net-(U10D-I0)") (class "Default")
      (node (ref "U10") (pin "12") (pinfunction "I0_12") (pintype "input"))
      (node (ref "U12") (pin "8") (pinfunction "O_8") (pintype "output"))
    )
    (net (code "78") (name "Net-(U10D-I1)") (class "Default")
      (node (ref "U10") (pin "13") (pinfunction "I1_13") (pintype "input"))
      (node (ref "U12") (pin "11") (pinfunction "O_11") (pintype "output"))
    )
    (net (code "79") (name "Net-(U13A-CLK)") (class "Default")
      (node (ref "R27") (pin "1") (pinfunction "1_1") (pintype "passive"))
      (node (ref "U13") (pin "1") (pinfunction "CLR_1") (pintype "input"))
      (node (ref "U13") (pin "2") (pinfunction "D_2") (pintype "input"))
      (node (ref "U13") (pin "3") (pinfunction "CLK_3") (pintype "input"))
      (node (ref "U13") (pin "4") (pinfunction "PRE_4") (pintype "input"))
    )
    (net (code "80") (name "Net-(U16A-OUT0)") (class "Default")
      (node (ref "CON2") (pin "3") (pinfunction "3_3") (pintype "passive"))
      (node (ref "U16") (pin "2") (pinfunction "OUT0_2") (pintype "bidirectional"))
    )
    (net (code "81") (name "Net-(U16A-OUT1)") (class "Default")
      (node (ref "CON2") (pin "9") (pinfunction "9_9") (pintype "passive"))
      (node (ref "U16") (pin "6") (pinfunction "OUT1_6") (pintype "bidirectional"))
    )
    (net (code "82") (name "Net-(U16A-~{OUT0})") (class "Default")
      (node (ref "CON2") (pin "5") (pinfunction "5_5") (pintype "passive"))
      (node (ref "U16") (pin "3") (pinfunction "~{OUT0}_3") (pintype "bidirectional"))
    )
    (net (code "83") (name "Net-(U16A-~{OUT1})") (class "Default")
      (node (ref "CON2") (pin "11") (pinfunction "11_11") (pintype "passive"))
      (node (ref "U16") (pin "5") (pinfunction "~{OUT1}_5") (pintype "bidirectional"))
    )
    (net (code "84") (name "Net-(U17A-D)") (class "Default")
      (node (ref "R15") (pin "2") (pinfunction "2_2") (pintype "passive"))
      (node (ref "U17") (pin "13") (pinfunction "CLR_13") (pintype "input"))
      (node (ref "U17") (pin "2") (pinfunction "D_2") (pintype "input"))
    )
    (net (code "85") (name "Net-(U20A-G2B)") (class "Default")
      (node (ref "JMPR2") (pin "P$2") (pinfunction "P$2_P$2") (pintype "passive"))
      (node (ref "JMPR3") (pin "P$2") (pinfunction "P$2_P$2") (pintype "passive"))
      (node (ref "JMPR4") (pin "P$2") (pinfunction "P$2_P$2") (pintype "passive"))
      (node (ref "JMPR5") (pin "P$2") (pinfunction "P$2_P$2") (pintype "passive"))
      (node (ref "JMPR6") (pin "P$2") (pinfunction "P$2_P$2") (pintype "passive"))
      (node (ref "JMPR7") (pin "P$2") (pinfunction "P$2_P$2") (pintype "passive"))
      (node (ref "JMPR8") (pin "P$2") (pinfunction "P$2_P$2") (pintype "passive"))
      (node (ref "U20") (pin "5") (pinfunction "G2B_5") (pintype "input"))
    )
    (net (code "86") (name "OSC1") (class "Default")
      (node (ref "U15") (pin "8") (pinfunction "O_8") (pintype "output"))
      (node (ref "U17") (pin "11") (pinfunction "CLK_11") (pintype "input"))
    )
    (net (code "87") (name "PA0") (class "Default")
      (node (ref "U4") (pin "5") (pinfunction "PA0_5") (pintype "bidirectional"))
      (node (ref "U8") (pin "2") (pinfunction "A_2") (pintype "input"))
    )
    (net (code "88") (name "PA1") (class "Default")
      (node (ref "U4") (pin "4") (pinfunction "PA1_4") (pintype "bidirectional"))
      (node (ref "U8") (pin "3") (pinfunction "B_3") (pintype "input"))
    )
    (net (code "89") (name "PA2") (class "Default")
      (node (ref "U4") (pin "3") (pinfunction "PA2_3") (pintype "bidirectional"))
      (node (ref "U8") (pin "4") (pinfunction "C_4") (pintype "input"))
    )
    (net (code "90") (name "PA3") (class "Default")
      (node (ref "U4") (pin "2") (pinfunction "PA3_2") (pintype "bidirectional"))
      (node (ref "U8") (pin "5") (pinfunction "D_5") (pintype "input"))
    )
    (net (code "91") (name "PA4") (class "Default")
      (node (ref "U4") (pin "44") (pinfunction "PA4_44") (pintype "bidirectional"))
      (node (ref "U8") (pin "10") (pinfunction "E_10") (pintype "input"))
    )
    (net (code "92") (name "PA5") (class "Default")
      (node (ref "U4") (pin "43") (pinfunction "PA5_43") (pintype "bidirectional"))
      (node (ref "U8") (pin "11") (pinfunction "F_11") (pintype "input"))
    )
    (net (code "93") (name "PA6") (class "Default")
      (node (ref "U4") (pin "42") (pinfunction "PA6_42") (pintype "bidirectional"))
      (node (ref "U8") (pin "12") (pinfunction "G_12") (pintype "input"))
    )
    (net (code "94") (name "PA7") (class "Default")
      (node (ref "U4") (pin "41") (pinfunction "PA7_41") (pintype "bidirectional"))
      (node (ref "U8") (pin "14") (pinfunction "H_14") (pintype "input"))
    )
    (net (code "95") (name "PCRST") (class "Default")
      (node (ref "R16") (pin "2") (pinfunction "2_2") (pintype "passive"))
      (node (ref "U15") (pin "1") (pinfunction "I_1") (pintype "input"))
      (node (ref "U4") (pin "16") (pinfunction "PC0_16") (pintype "bidirectional"))
    )
    (net (code "96") (name "PU502") (class "Default")
      (node (ref "R2") (pin "1") (pinfunction "1_1") (pintype "passive"))
      (node (ref "U14") (pin "6") (pinfunction "D_6") (pintype "input"))
      (node (ref "U9") (pin "1") (pinfunction "CLR_1") (pintype "input"))
    )
    (net (code "97") (name "RCO") (class "Default")
      (node (ref "U12") (pin "2") (pinfunction "I1_2") (pintype "input"))
      (node (ref "U12") (pin "4") (pinfunction "I0_4") (pintype "input"))
      (node (ref "U14") (pin "15") (pinfunction "CO_15") (pintype "output"))
    )
    (net (code "98") (name "RDBAK") (class "Default")
      (node (ref "U18") (pin "13") (pinfunction "O_13") (pintype "output"))
      (node (ref "U3") (pin "4") (pinfunction "G_4") (pintype "bidirectional"))
    )
    (net (code "99") (name "RST") (class "Default")
      (node (ref "U4") (pin "39") (pinfunction "RESET_39") (pintype "input"))
      (node (ref "X2") (pin "B2") (pinfunction "RESETDRV_B2") (pintype "passive"))
    )
    (net (code "100") (name "SCOPE") (class "Default")
      (node (ref "U11") (pin "4") (pinfunction "O_4") (pintype "output"))
      (node (ref "U16") (pin "7") (pinfunction "IN1_7") (pintype "bidirectional"))
      (node (ref "U4") (pin "27") (pinfunction "PB6_27") (pintype "bidirectional"))
    )
    (net (code "101") (name "SHIFTIN") (class "Default")
      (node (ref "U7") (pin "19") (pinfunction "Q8_19") (pintype "output"))
      (node (ref "U8") (pin "1") (pinfunction "SER_1") (pintype "input"))
    )
    (net (code "102") (name "UNDERFLOW") (class "Default")
      (node (ref "U13") (pin "8") (pinfunction "~{Q}_8") (pintype "output"))
      (node (ref "U4") (pin "20") (pinfunction "PB0_20") (pintype "bidirectional"))
    )
    (net (code "103") (name "VCC") (class "Default")
      (node (ref "C1") (pin "1") (pinfunction "1_1") (pintype "passive"))
      (node (ref "C10") (pin "1") (pinfunction "1_1") (pintype "passive"))
      (node (ref "C12") (pin "1") (pinfunction "1_1") (pintype "passive"))
      (node (ref "C13") (pin "1") (pinfunction "1_1") (pintype "passive"))
      (node (ref "C14") (pin "1") (pinfunction "1_1") (pintype "passive"))
      (node (ref "C15") (pin "1") (pinfunction "1_1") (pintype "passive"))
      (node (ref "C16") (pin "1") (pinfunction "1_1") (pintype "passive"))
      (node (ref "C17") (pin "1") (pinfunction "1_1") (pintype "passive"))
      (node (ref "C18") (pin "1") (pinfunction "1_1") (pintype "passive"))
      (node (ref "C19") (pin "1") (pinfunction "1_1") (pintype "passive"))
      (node (ref "C2") (pin "1") (pinfunction "1_1") (pintype "passive"))
      (node (ref "C20") (pin "1") (pinfunction "1_1") (pintype "passive"))
      (node (ref "C4") (pin "1") (pinfunction "1_1") (pintype "passive"))
      (node (ref "C5") (pin "1") (pinfunction "1_1") (pintype "passive"))
      (node (ref "C6") (pin "1") (pinfunction "1_1") (pintype "passive"))
      (node (ref "C7") (pin "1") (pinfunction "1_1") (pintype "passive"))
      (node (ref "C8") (pin "1") (pinfunction "1_1") (pintype "passive"))
      (node (ref "C9") (pin "1") (pinfunction "1_1") (pintype "passive"))
      (node (ref "CON2") (pin "15") (pinfunction "15_15") (pintype "passive"))
      (node (ref "R1") (pin "2") (pinfunction "2_2") (pintype "passive"))
      (node (ref "R10") (pin "1") (pinfunction "1_1") (pintype "passive"))
      (node (ref "R11") (pin "1") (pinfunction "1_1") (pintype "passive"))
      (node (ref "R12") (pin "1") (pinfunction "1_1") (pintype "passive"))
      (node (ref "R13") (pin "1") (pinfunction "1_1") (pintype "passive"))
      (node (ref "R14") (pin "1") (pinfunction "1_1") (pintype "passive"))
      (node (ref "R15") (pin "1") (pinfunction "1_1") (pintype "passive"))
      (node (ref "R16") (pin "1") (pinfunction "1_1") (pintype "passive"))
      (node (ref "R17") (pin "1") (pinfunction "1_1") (pintype "passive"))
      (node (ref "R18") (pin "1") (pinfunction "1_1") (pintype "passive"))
      (node (ref "R2") (pin "2") (pinfunction "2_2") (pintype "passive"))
      (node (ref "R27") (pin "2") (pinfunction "2_2") (pintype "passive"))
      (node (ref "R7") (pin "1") (pinfunction "1_1") (pintype "passive"))
      (node (ref "R8") (pin "1") (pinfunction "1_1") (pintype "passive"))
      (node (ref "R9") (pin "1") (pinfunction "1_1") (pintype "passive"))
      (node (ref "U1") (pin "16") (pinfunction "VCC_16") (pintype "power_in"))
      (node (ref "U10") (pin "14") (pinfunction "VCC_14") (pintype "power_in"))
      (node (ref "U11") (pin "14") (pinfunction "VCC_14") (pintype "power_in"))
      (node (ref "U12") (pin "14") (pinfunction "VCC_14") (pintype "power_in"))
      (node (ref "U13") (pin "14") (pinfunction "VCC_14") (pintype "power_in"))
      (node (ref "U14") (pin "16") (pinfunction "VCC_16") (pintype "power_in"))
      (node (ref "U15") (pin "14") (pinfunction "VCC_14") (pintype "power_in"))
      (node (ref "U16") (pin "16") (pinfunction "VCC_16") (pintype "power_in"))
      (node (ref "U17") (pin "14") (pinfunction "VCC_14") (pintype "power_in"))
      (node (ref "U18") (pin "14") (pinfunction "VCC_14") (pintype "power_in"))
      (node (ref "U20") (pin "6") (pinfunction "G1_6") (pintype "input"))
      (node (ref "U3") (pin "12") (pinfunction "~{G}_12") (pintype "bidirectional"))
      (node (ref "U3") (pin "16") (pinfunction "VCC_16") (pintype "power_in"))
      (node (ref "U4") (pin "29") (pinfunction "VCC_29") (pintype "power_in"))
      (node (ref "U5") (pin "13") (pinfunction "G0_13") (pintype "bidirectional"))
      (node (ref "U5") (pin "19") (pinfunction "G2_19") (pintype "bidirectional"))
      (node (ref "U5") (pin "28") (pinfunction "VCC_28") (pintype "power_in"))
      (node (ref "U6") (pin "20") (pinfunction "VCC_20") (pintype "power_in"))
      (node (ref "U7") (pin "20") (pinfunction "VCC_20") (pintype "power_in"))
      (node (ref "U8") (pin "16") (pinfunction "VCC_16") (pintype "power_in"))
      (node (ref "U9") (pin "14") (pinfunction "VCC_14") (pintype "power_in"))
      (node (ref "X1") (pin "4") (pinfunction "VDD_4") (pintype "power_in"))
      (node (ref "X2") (pin "B29") (pinfunction "+5V_B29") (pintype "passive"))
      (node (ref "X2") (pin "B3") (pinfunction "+5V_B3") (pintype "passive"))
    )
    (net (code "104") (name "unconnected-(CON2-Pad26)") (class "Default")
      (node (ref "CON2") (pin "26") (pinfunction "26_26") (pintype "passive"))
    )
    (net (code "105") (name "unconnected-(U1A-Y0-Pad15)") (class "Default")
      (node (ref "U1") (pin "15") (pinfunction "Y0_15") (pintype "output"))
    )
    (net (code "106") (name "unconnected-(U7A-Q7-Pad16)") (class "Default")
      (node (ref "U7") (pin "16") (pinfunction "Q7_16") (pintype "output"))
    )
    (net (code "107") (name "unconnected-(U13A-Q-Pad5)") (class "Default")
      (node (ref "U13") (pin "5") (pinfunction "Q_5") (pintype "output"))
    )
    (net (code "108") (name "unconnected-(U13A-~{Q}-Pad6)") (class "Default")
      (node (ref "U13") (pin "6") (pinfunction "~{Q}_6") (pintype "output"))
    )
    (net (code "109") (name "unconnected-(U14A-QA-Pad14)") (class "Default")
      (node (ref "U14") (pin "14") (pinfunction "QA_14") (pintype "output"))
    )
    (net (code "110") (name "unconnected-(U14A-QB-Pad13)") (class "Default")
      (node (ref "U14") (pin "13") (pinfunction "QB_13") (pintype "output"))
    )
    (net (code "111") (name "unconnected-(U14A-QC-Pad12)") (class "Default")
      (node (ref "U14") (pin "12") (pinfunction "QC_12") (pintype "output"))
    )
    (net (code "112") (name "unconnected-(U14A-QD-Pad11)") (class "Default")
      (node (ref "U14") (pin "11") (pinfunction "QD_11") (pintype "output"))
    )
    (net (code "113") (name "unconnected-(U16A-OUT2-Pad10)") (class "Default")
      (node (ref "U16") (pin "10") (pinfunction "OUT2_10") (pintype "bidirectional"))
    )
    (net (code "114") (name "unconnected-(U16A-OUT3-Pad14)") (class "Default")
      (node (ref "U16") (pin "14") (pinfunction "OUT3_14") (pintype "bidirectional"))
    )
    (net (code "115") (name "unconnected-(U17A-~{Q}-Pad6)") (class "Default")
      (node (ref "U17") (pin "6") (pinfunction "~{Q}_6") (pintype "output"))
    )
    (net (code "116") (name "unconnected-(U20A-Y3-Pad12)") (class "Default")
      (node (ref "U20") (pin "12") (pinfunction "Y3_12") (pintype "output"))
    )
    (net (code "117") (name "unconnected-(U20A-Y6-Pad9)") (class "Default")
      (node (ref "U20") (pin "9") (pinfunction "Y6_9") (pintype "output"))
    )
    (net (code "118") (name "unconnected-(U20A-Y7-Pad7)") (class "Default")
      (node (ref "U20") (pin "7") (pinfunction "Y7_7") (pintype "output"))
    )
    (net (code "119") (name "unconnected-(X1-CON-Pad1)") (class "Default")
      (node (ref "X1") (pin "1") (pinfunction "CON_1") (pintype "input"))
    )
    (net (code "120") (name "unconnected-(X2A-+12V-PadB9)") (class "Default")
      (node (ref "X2") (pin "B9") (pinfunction "+12V_B9") (pintype "passive"))
    )
    (net (code "121") (name "unconnected-(X2A--5V-PadB5)") (class "Default")
      (node (ref "X2") (pin "B5") (pinfunction "-5V_B5") (pintype "passive"))
    )
    (net (code "122") (name "unconnected-(X2A--12V-PadB7)") (class "Default")
      (node (ref "X2") (pin "B7") (pinfunction "-12V_B7") (pintype "passive"))
    )
    (net (code "123") (name "unconnected-(X2A-BALE-PadB28)") (class "Default")
      (node (ref "X2") (pin "B28") (pinfunction "BALE_B28") (pintype "passive"))
    )
    (net (code "124") (name "unconnected-(X2A-DACK1-PadB17)") (class "Default")
      (node (ref "X2") (pin "B17") (pinfunction "DACK1_B17") (pintype "passive"))
    )
    (net (code "125") (name "unconnected-(X2A-DACK2-PadB26)") (class "Default")
      (node (ref "X2") (pin "B26") (pinfunction "DACK2_B26") (pintype "passive"))
    )
    (net (code "126") (name "unconnected-(X2A-DACK3-PadB15)") (class "Default")
      (node (ref "X2") (pin "B15") (pinfunction "DACK3_B15") (pintype "passive"))
    )
    (net (code "127") (name "unconnected-(X2A-DRQ1-PadB18)") (class "Default")
      (node (ref "X2") (pin "B18") (pinfunction "DRQ1_B18") (pintype "passive"))
    )
    (net (code "128") (name "unconnected-(X2A-DRQ2-PadB6)") (class "Default")
      (node (ref "X2") (pin "B6") (pinfunction "DRQ2_B6") (pintype "passive"))
    )
    (net (code "129") (name "unconnected-(X2A-DRQ3-PadB16)") (class "Default")
      (node (ref "X2") (pin "B16") (pinfunction "DRQ3_B16") (pintype "passive"))
    )
    (net (code "130") (name "unconnected-(X2A-ENDXFR-PadB8)") (class "Default")
      (node (ref "X2") (pin "B8") (pinfunction "ENDXFR_B8") (pintype "passive"))
    )
    (net (code "131") (name "unconnected-(X2A-IOCHCHK-PadA1)") (class "Default")
      (node (ref "X2") (pin "A1") (pinfunction "IOCHCHK_A1") (pintype "passive"))
    )
    (net (code "132") (name "unconnected-(X2A-IOCHRDY-PadA10)") (class "Default")
      (node (ref "X2") (pin "A10") (pinfunction "IOCHRDY_A10") (pintype "passive"))
    )
    (net (code "133") (name "unconnected-(X2A-IRQ3-PadB25)") (class "Default")
      (node (ref "X2") (pin "B25") (pinfunction "IRQ3_B25") (pintype "passive"))
    )
    (net (code "134") (name "unconnected-(X2A-IRQ4-PadB24)") (class "Default")
      (node (ref "X2") (pin "B24") (pinfunction "IRQ4_B24") (pintype "passive"))
    )
    (net (code "135") (name "unconnected-(X2A-IRQ5-PadB23)") (class "Default")
      (node (ref "X2") (pin "B23") (pinfunction "IRQ5_B23") (pintype "passive"))
    )
    (net (code "136") (name "unconnected-(X2A-IRQ6-PadB22)") (class "Default")
      (node (ref "X2") (pin "B22") (pinfunction "IRQ6_B22") (pintype "passive"))
    )
    (net (code "137") (name "unconnected-(X2A-IRQ7-PadB21)") (class "Default")
      (node (ref "X2") (pin "B21") (pinfunction "IRQ7_B21") (pintype "passive"))
    )
    (net (code "138") (name "unconnected-(X2A-IRQ9-PadB4)") (class "Default")
      (node (ref "X2") (pin "B4") (pinfunction "IRQ9_B4") (pintype "passive"))
    )
    (net (code "139") (name "unconnected-(X2A-KEY-PadB10)") (class "Default")
      (node (ref "X2") (pin "B10") (pinfunction "KEY_B10") (pintype "passive"))
    )
    (net (code "140") (name "unconnected-(X2A-OSC-PadB30)") (class "Default")
      (node (ref "X2") (pin "B30") (pinfunction "OSC_B30") (pintype "passive"))
    )
    (net (code "141") (name "unconnected-(X2A-REFRESH-PadB19)") (class "Default")
      (node (ref "X2") (pin "B19") (pinfunction "REFRESH_B19") (pintype "passive"))
    )
    (net (code "142") (name "unconnected-(X2A-SA10-PadA21)") (class "Default")
      (node (ref "X2") (pin "A21") (pinfunction "SA10_A21") (pintype "passive"))
    )
    (net (code "143") (name "unconnected-(X2A-SA11-PadA20)") (class "Default")
      (node (ref "X2") (pin "A20") (pinfunction "SA11_A20") (pintype "passive"))
    )
    (net (code "144") (name "unconnected-(X2A-SA12-PadA19)") (class "Default")
      (node (ref "X2") (pin "A19") (pinfunction "SA12_A19") (pintype "passive"))
    )
    (net (code "145") (name "unconnected-(X2A-SA13-PadA18)") (class "Default")
      (node (ref "X2") (pin "A18") (pinfunction "SA13_A18") (pintype "passive"))
    )
    (net (code "146") (name "unconnected-(X2A-SA14-PadA17)") (class "Default")
      (node (ref "X2") (pin "A17") (pinfunction "SA14_A17") (pintype "passive"))
    )
    (net (code "147") (name "unconnected-(X2A-SA15-PadA16)") (class "Default")
      (node (ref "X2") (pin "A16") (pinfunction "SA15_A16") (pintype "passive"))
    )
    (net (code "148") (name "unconnected-(X2A-SA16-PadA15)") (class "Default")
      (node (ref "X2") (pin "A15") (pinfunction "SA16_A15") (pintype "passive"))
    )
    (net (code "149") (name "unconnected-(X2A-SA17-PadA14)") (class "Default")
      (node (ref "X2") (pin "A14") (pinfunction "SA17_A14") (pintype "passive"))
    )
    (net (code "150") (name "unconnected-(X2A-SA18-PadA13)") (class "Default")
      (node (ref "X2") (pin "A13") (pinfunction "SA18_A13") (pintype "passive"))
    )
    (net (code "151") (name "unconnected-(X2A-SA19-PadA12)") (class "Default")
      (node (ref "X2") (pin "A12") (pinfunction "SA19_A12") (pintype "passive"))
    )
    (net (code "152") (name "unconnected-(X2A-SMEMR-PadB12)") (class "Default")
      (node (ref "X2") (pin "B12") (pinfunction "SMEMR_B12") (pintype "passive"))
    )
    (net (code "153") (name "unconnected-(X2A-SMEMW-PadB11)") (class "Default")
      (node (ref "X2") (pin "B11") (pinfunction "SMEMW_B11") (pintype "passive"))
    )
    (net (code "154") (name "unconnected-(X2A-SYSCLK-PadB20)") (class "Default")
      (node (ref "X2") (pin "B20") (pinfunction "SYSCLK_B20") (pintype "passive"))
    )
    (net (code "155") (name "unconnected-(X2A-TC-PadB27)") (class "Default")
      (node (ref "X2") (pin "B27") (pinfunction "TC_B27") (pintype "passive"))
    )
    (net (code "156") (name "~{AE}") (class "Default")
      (node (ref "U1") (pin "4") (pinfunction "G2A_4") (pintype "input"))
      (node (ref "X2") (pin "A11") (pinfunction "AEN_A11") (pintype "passive"))
    )
    (net (code "157") (name "~{AUXIN}") (class "Default")
      (node (ref "U16") (pin "11") (pinfunction "~{OUT2}_11") (pintype "bidirectional"))
      (node (ref "U6") (pin "1") (pinfunction "1G_1") (pintype "bidirectional"))
      (node (ref "U6") (pin "19") (pinfunction "2G_19") (pintype "bidirectional"))
    )
    (net (code "158") (name "~{AUXOUT}") (class "Default")
      (node (ref "U16") (pin "13") (pinfunction "~{OUT3}_13") (pintype "bidirectional"))
      (node (ref "U7") (pin "11") (pinfunction "CLK_11") (pintype "input"))
    )
    (net (code "159") (name "~{CLK1}") (class "Default")
      (node (ref "U15") (pin "6") (pinfunction "O_6") (pintype "output"))
      (node (ref "U4") (pin "21") (pinfunction "PB1_21") (pintype "bidirectional"))
      (node (ref "U5") (pin "18") (pinfunction "CLK1_18") (pintype "bidirectional"))
      (node (ref "U9") (pin "11") (pinfunction "CLK_11") (pintype "input"))
    )
    (net (code "160") (name "~{CPUCLK}") (class "Default")
      (node (ref "U12") (pin "9") (pinfunction "I0_9") (pintype "input"))
      (node (ref "U4") (pin "18") (pinfunction "PC2_18") (pintype "bidirectional"))
    )
    (net (code "161") (name "~{DATALD}") (class "Default")
      (node (ref "U11") (pin "5") (pinfunction "I0_5") (pintype "input"))
      (node (ref "U12") (pin "6") (pinfunction "O_6") (pintype "output"))
      (node (ref "U14") (pin "9") (pinfunction "LD_9") (pintype "input"))
      (node (ref "U4") (pin "13") (pinfunction "PC6_13") (pintype "bidirectional"))
      (node (ref "U8") (pin "15") (pinfunction "SH/~{LD}_15") (pintype "input"))
      (node (ref "U9") (pin "13") (pinfunction "CLR_13") (pintype "input"))
    )
    (net (code "162") (name "~{DATARDY}") (class "Default")
      (node (ref "U12") (pin "1") (pinfunction "I0_1") (pintype "input"))
      (node (ref "U9") (pin "9") (pinfunction "Q_9") (pintype "output"))
    )
    (net (code "163") (name "~{DCCOUTD}") (class "Default")
      (node (ref "U10") (pin "1") (pinfunction "I0_1") (pintype "input"))
      (node (ref "U9") (pin "6") (pinfunction "~{Q}_6") (pintype "output"))
    )
    (net (code "164") (name "~{DCCOUT}") (class "Default")
      (node (ref "U14") (pin "10") (pinfunction "TE_10") (pintype "input"))
      (node (ref "U15") (pin "10") (pinfunction "O_10") (pintype "output"))
    )
    (net (code "165") (name "~{LCPUEN}") (class "Default")
      (node (ref "U12") (pin "12") (pinfunction "I0_12") (pintype "input"))
      (node (ref "U17") (pin "8") (pinfunction "~{Q}_8") (pintype "output"))
    )
    (net (code "166") (name "~{OBFA}") (class "Default")
      (node (ref "U4") (pin "11") (pinfunction "PC7_11") (pintype "bidirectional"))
      (node (ref "U9") (pin "12") (pinfunction "D_12") (pintype "input"))
    )
    (net (code "167") (name "~{OSC1}") (class "Default")
      (node (ref "U12") (pin "13") (pinfunction "I1_13") (pintype "input"))
      (node (ref "U15") (pin "9") (pinfunction "I_9") (pintype "input"))
      (node (ref "X1") (pin "3") (pinfunction "OUT_3") (pintype "output"))
    )
    (net (code "168") (name "~{PCRST}") (class "Default")
      (node (ref "U13") (pin "13") (pinfunction "CLR_13") (pintype "input"))
      (node (ref "U14") (pin "1") (pinfunction "~{CL}_1") (pintype "input"))
      (node (ref "U15") (pin "2") (pinfunction "O_2") (pintype "output"))
      (node (ref "U17") (pin "10") (pinfunction "PRE_10") (pintype "input"))
      (node (ref "U17") (pin "4") (pinfunction "PRE_4") (pintype "input"))
      (node (ref "U7") (pin "1") (pinfunction "CLR_1") (pintype "input"))
      (node (ref "U8") (pin "9") (pinfunction "CLR_9") (pintype "input"))
      (node (ref "U9") (pin "10") (pinfunction "PRE_10") (pintype "input"))
      (node (ref "U9") (pin "4") (pinfunction "PRE_4") (pintype "input"))
    )
    (net (code "169") (name "~{RD}") (class "Default")
      (node (ref "U18") (pin "11") (pinfunction "I0_11") (pintype "input"))
      (node (ref "U18") (pin "5") (pinfunction "I0_5") (pintype "input"))
      (node (ref "U4") (pin "6") (pinfunction "RD_6") (pintype "input"))
      (node (ref "U5") (pin "26") (pinfunction "RD_26") (pintype "input"))
      (node (ref "X2") (pin "B14") (pinfunction "IOR_B14") (pintype "passive"))
    )
    (net (code "170") (name "~{SCOPE_ENBL}") (class "Default")
      (node (ref "U11") (pin "6") (pinfunction "I1_6") (pintype "input"))
      (node (ref "U4") (pin "14") (pinfunction "PC5_14") (pintype "bidirectional"))
    )
    (net (code "171") (name "~{SEL0}") (class "Default")
      (node (ref "U18") (pin "12") (pinfunction "I1_12") (pintype "input"))
      (node (ref "U20") (pin "15") (pinfunction "Y0_15") (pintype "output"))
    )
    (net (code "172") (name "~{SEL1}") (class "Default")
      (node (ref "U18") (pin "6") (pinfunction "I1_6") (pintype "input"))
      (node (ref "U20") (pin "14") (pinfunction "Y1_14") (pintype "output"))
    )
    (net (code "173") (name "~{SEL2}") (class "Default")
      (node (ref "U18") (pin "9") (pinfunction "I1_9") (pintype "input"))
      (node (ref "U20") (pin "13") (pinfunction "Y2_13") (pintype "output"))
    )
    (net (code "174") (name "~{SEL8254}") (class "Default")
      (node (ref "U20") (pin "10") (pinfunction "Y5_10") (pintype "output"))
      (node (ref "U5") (pin "24") (pinfunction "CS_24") (pintype "input"))
    )
    (net (code "175") (name "~{SEL8255}") (class "Default")
      (node (ref "U20") (pin "11") (pinfunction "Y4_11") (pintype "output"))
      (node (ref "U4") (pin "7") (pinfunction "CS_7") (pintype "input"))
    )
    (net (code "176") (name "~{SHOLD}") (class "Default")
      (node (ref "U10") (pin "5") (pinfunction "I1_5") (pintype "input"))
      (node (ref "U12") (pin "3") (pinfunction "O_3") (pintype "output"))
      (node (ref "U14") (pin "7") (pinfunction "PE_7") (pintype "input"))
      (node (ref "U4") (pin "26") (pinfunction "PB5_26") (pintype "bidirectional"))
    )
    (net (code "177") (name "~{UNDERCLR}") (class "Default")
      (node (ref "R18") (pin "2") (pinfunction "2_2") (pintype "passive"))
      (node (ref "U13") (pin "10") (pinfunction "PRE_10") (pintype "input"))
      (node (ref "U4") (pin "15") (pinfunction "PC4_15") (pintype "bidirectional"))
    )
    (net (code "178") (name "~{WR}") (class "Default")
      (node (ref "U18") (pin "8") (pinfunction "I0_8") (pintype "input"))
      (node (ref "U4") (pin "40") (pinfunction "WR_40") (pintype "input"))
      (node (ref "U5") (pin "27") (pinfunction "WR_27") (pintype "input"))
      (node (ref "X2") (pin "B13") (pinfunction "IOW_B13") (pintype "passive"))
    )
  )
)
